# DAC5682.net
KiCad netlist of a schematic drawn in Altium Designer
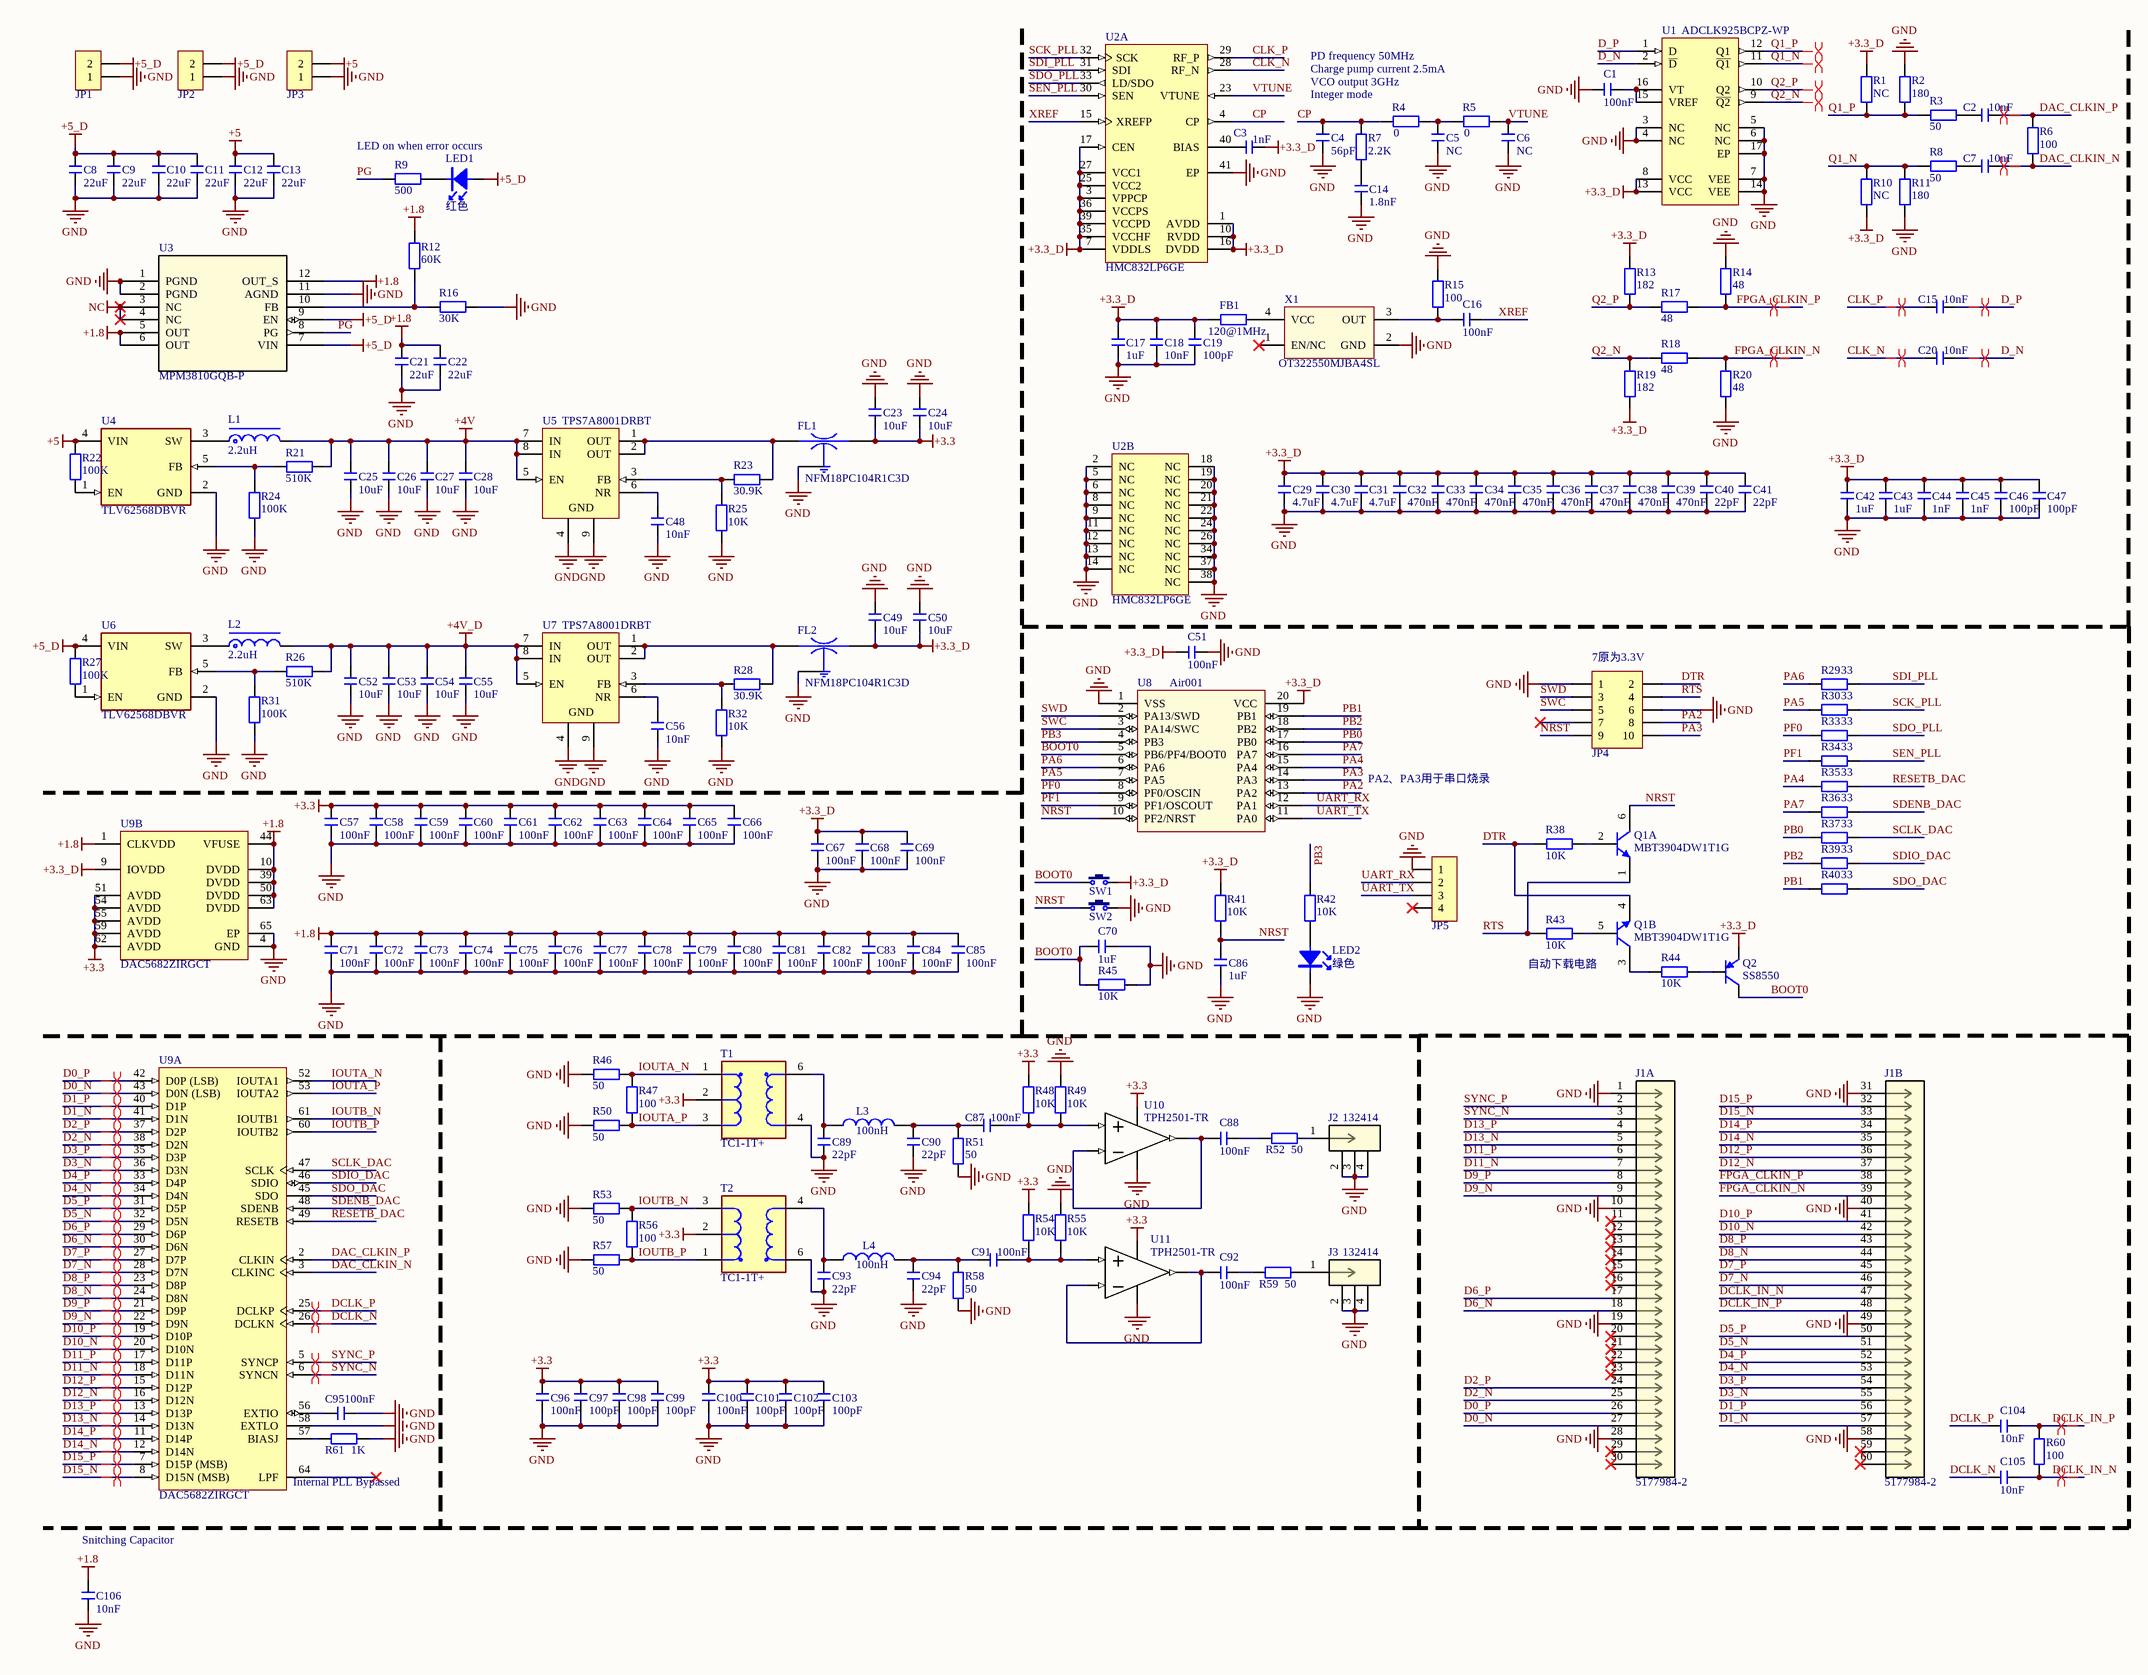
[diagram p0: DAC5682.SchDoc]

(export (version "E")
  (design (tool "Eeschema 10.0.6"))
  (components
    (comp (ref "C1")
      (value "100nF")
      (footprint "C 0402_L")
      (description "贴片电容")
      (libsource (lib "01 - 电容-电阻-电感") (part "C"))
    )
    (comp (ref "C2")
      (value "10nF")
      (footprint "C 0402_L")
      (description "贴片电容")
      (libsource (lib "01 - 电容-电阻-电感") (part "C"))
    )
    (comp (ref "C3")
      (value "1nF")
      (footprint "C 0402_L")
      (description "贴片电容")
      (libsource (lib "01 - 电容-电阻-电感") (part "C"))
    )
    (comp (ref "C4")
      (value "56pF")
      (footprint "C 0402_L")
      (description "贴片电容")
      (libsource (lib "01 - 电容-电阻-电感") (part "C"))
    )
    (comp (ref "C5")
      (value "NC")
      (footprint "C 0402_L")
      (description "贴片电容")
      (libsource (lib "01 - 电容-电阻-电感") (part "C"))
    )
    (comp (ref "C6")
      (value "NC")
      (footprint "C 0402_L")
      (description "贴片电容")
      (libsource (lib "01 - 电容-电阻-电感") (part "C"))
    )
    (comp (ref "C7")
      (value "10nF")
      (footprint "C 0402_L")
      (description "贴片电容")
      (libsource (lib "01 - 电容-电阻-电感") (part "C"))
    )
    (comp (ref "C8")
      (value "22uF")
      (footprint "C 1206_L")
      (description "贴片电容")
      (libsource (lib "01 - 电容-电阻-电感") (part "C"))
    )
    (comp (ref "C9")
      (value "22uF")
      (footprint "C 1206_L")
      (description "贴片电容")
      (libsource (lib "01 - 电容-电阻-电感") (part "C"))
    )
    (comp (ref "C10")
      (value "22uF")
      (footprint "C 1206_L")
      (description "贴片电容")
      (libsource (lib "01 - 电容-电阻-电感") (part "C"))
    )
    (comp (ref "C11")
      (value "22uF")
      (footprint "C 1206_L")
      (description "贴片电容")
      (libsource (lib "01 - 电容-电阻-电感") (part "C"))
    )
    (comp (ref "C12")
      (value "22uF")
      (footprint "C 1206_L")
      (description "贴片电容")
      (libsource (lib "01 - 电容-电阻-电感") (part "C"))
    )
    (comp (ref "C13")
      (value "22uF")
      (footprint "C 1206_L")
      (description "贴片电容")
      (libsource (lib "01 - 电容-电阻-电感") (part "C"))
    )
    (comp (ref "C14")
      (value "1.8nF")
      (footprint "C 0402_L")
      (description "贴片电容")
      (libsource (lib "01 - 电容-电阻-电感") (part "C"))
    )
    (comp (ref "C15")
      (value "10nF")
      (footprint "C 0402_L")
      (description "贴片电容")
      (libsource (lib "01 - 电容-电阻-电感") (part "C"))
    )
    (comp (ref "C16")
      (value "100nF")
      (footprint "C 0402_L")
      (description "贴片电容")
      (libsource (lib "01 - 电容-电阻-电感") (part "C"))
    )
    (comp (ref "C17")
      (value "1uF")
      (footprint "C 0402_L")
      (description "贴片电容")
      (libsource (lib "01 - 电容-电阻-电感") (part "C"))
    )
    (comp (ref "C18")
      (value "10nF")
      (footprint "C 0402_L")
      (description "贴片电容")
      (libsource (lib "01 - 电容-电阻-电感") (part "C"))
    )
    (comp (ref "C19")
      (value "100pF")
      (footprint "C 0402_L")
      (description "贴片电容")
      (libsource (lib "01 - 电容-电阻-电感") (part "C"))
    )
    (comp (ref "C20")
      (value "10nF")
      (footprint "C 0402_L")
      (description "贴片电容")
      (libsource (lib "01 - 电容-电阻-电感") (part "C"))
    )
    (comp (ref "C21")
      (value "22uF")
      (footprint "C 1206_L")
      (description "贴片电容")
      (libsource (lib "01 - 电容-电阻-电感") (part "C"))
    )
    (comp (ref "C22")
      (value "22uF")
      (footprint "C 1206_L")
      (description "贴片电容")
      (libsource (lib "01 - 电容-电阻-电感") (part "C"))
    )
    (comp (ref "C23")
      (value "10uF")
      (footprint "C 0805_L")
      (description "贴片电容")
      (libsource (lib "01 - 电容-电阻-电感") (part "C"))
    )
    (comp (ref "C24")
      (value "10uF")
      (footprint "C 0805_L")
      (description "贴片电容")
      (libsource (lib "01 - 电容-电阻-电感") (part "C"))
    )
    (comp (ref "C25")
      (value "10uF")
      (footprint "C 0805_L")
      (description "贴片电容")
      (libsource (lib "01 - 电容-电阻-电感") (part "C"))
    )
    (comp (ref "C26")
      (value "10uF")
      (footprint "C 0805_L")
      (description "贴片电容")
      (libsource (lib "01 - 电容-电阻-电感") (part "C"))
    )
    (comp (ref "C27")
      (value "10uF")
      (footprint "C 0805_L")
      (description "贴片电容")
      (libsource (lib "01 - 电容-电阻-电感") (part "C"))
    )
    (comp (ref "C28")
      (value "10uF")
      (footprint "C 0805_L")
      (description "贴片电容")
      (libsource (lib "01 - 电容-电阻-电感") (part "C"))
    )
    (comp (ref "C29")
      (value "4.7uF")
      (footprint "C 0603_L")
      (description "贴片电容")
      (libsource (lib "01 - 电容-电阻-电感") (part "C"))
    )
    (comp (ref "C30")
      (value "4.7uF")
      (footprint "C 0603_L")
      (description "贴片电容")
      (libsource (lib "01 - 电容-电阻-电感") (part "C"))
    )
    (comp (ref "C31")
      (value "4.7uF")
      (footprint "C 0603_L")
      (description "贴片电容")
      (libsource (lib "01 - 电容-电阻-电感") (part "C"))
    )
    (comp (ref "C32")
      (value "470nF")
      (footprint "C 0402_L")
      (description "贴片电容")
      (libsource (lib "01 - 电容-电阻-电感") (part "C"))
    )
    (comp (ref "C33")
      (value "470nF")
      (footprint "C 0402_L")
      (description "贴片电容")
      (libsource (lib "01 - 电容-电阻-电感") (part "C"))
    )
    (comp (ref "C34")
      (value "470nF")
      (footprint "C 0402_L")
      (description "贴片电容")
      (libsource (lib "01 - 电容-电阻-电感") (part "C"))
    )
    (comp (ref "C35")
      (value "470nF")
      (footprint "C 0402_L")
      (description "贴片电容")
      (libsource (lib "01 - 电容-电阻-电感") (part "C"))
    )
    (comp (ref "C36")
      (value "470nF")
      (footprint "C 0402_L")
      (description "贴片电容")
      (libsource (lib "01 - 电容-电阻-电感") (part "C"))
    )
    (comp (ref "C37")
      (value "470nF")
      (footprint "C 0402_L")
      (description "贴片电容")
      (libsource (lib "01 - 电容-电阻-电感") (part "C"))
    )
    (comp (ref "C38")
      (value "470nF")
      (footprint "C 0402_L")
      (description "贴片电容")
      (libsource (lib "01 - 电容-电阻-电感") (part "C"))
    )
    (comp (ref "C39")
      (value "470nF")
      (footprint "C 0402_L")
      (description "贴片电容")
      (libsource (lib "01 - 电容-电阻-电感") (part "C"))
    )
    (comp (ref "C40")
      (value "22pF")
      (footprint "C 0402_L")
      (description "贴片电容")
      (libsource (lib "01 - 电容-电阻-电感") (part "C"))
    )
    (comp (ref "C41")
      (value "22pF")
      (footprint "C 0402_L")
      (description "贴片电容")
      (libsource (lib "01 - 电容-电阻-电感") (part "C"))
    )
    (comp (ref "C42")
      (value "1uF")
      (footprint "C 0603_L")
      (description "贴片电容")
      (libsource (lib "01 - 电容-电阻-电感") (part "C"))
    )
    (comp (ref "C43")
      (value "1uF")
      (footprint "C 0603_L")
      (description "贴片电容")
      (libsource (lib "01 - 电容-电阻-电感") (part "C"))
    )
    (comp (ref "C44")
      (value "1nF")
      (footprint "C 0402_L")
      (description "贴片电容")
      (libsource (lib "01 - 电容-电阻-电感") (part "C"))
    )
    (comp (ref "C45")
      (value "1nF")
      (footprint "C 0402_L")
      (description "贴片电容")
      (libsource (lib "01 - 电容-电阻-电感") (part "C"))
    )
    (comp (ref "C46")
      (value "100pF")
      (footprint "C 0402_L")
      (description "贴片电容")
      (libsource (lib "01 - 电容-电阻-电感") (part "C"))
    )
    (comp (ref "C47")
      (value "100pF")
      (footprint "C 0402_L")
      (description "贴片电容")
      (libsource (lib "01 - 电容-电阻-电感") (part "C"))
    )
    (comp (ref "C48")
      (value "10nF")
      (footprint "C 0402_L")
      (description "贴片电容")
      (libsource (lib "01 - 电容-电阻-电感") (part "C"))
    )
    (comp (ref "C49")
      (value "10uF")
      (footprint "C 0805_L")
      (description "贴片电容")
      (libsource (lib "01 - 电容-电阻-电感") (part "C"))
    )
    (comp (ref "C50")
      (value "10uF")
      (footprint "C 0805_L")
      (description "贴片电容")
      (libsource (lib "01 - 电容-电阻-电感") (part "C"))
    )
    (comp (ref "C51")
      (value "100nF")
      (footprint "C 0402_L")
      (description "贴片电容")
      (libsource (lib "01 - 电容-电阻-电感") (part "C"))
    )
    (comp (ref "C52")
      (value "10uF")
      (footprint "C 0805_L")
      (description "贴片电容")
      (libsource (lib "01 - 电容-电阻-电感") (part "C"))
    )
    (comp (ref "C53")
      (value "10uF")
      (footprint "C 0805_L")
      (description "贴片电容")
      (libsource (lib "01 - 电容-电阻-电感") (part "C"))
    )
    (comp (ref "C54")
      (value "10uF")
      (footprint "C 0805_L")
      (description "贴片电容")
      (libsource (lib "01 - 电容-电阻-电感") (part "C"))
    )
    (comp (ref "C55")
      (value "10uF")
      (footprint "C 0805_L")
      (description "贴片电容")
      (libsource (lib "01 - 电容-电阻-电感") (part "C"))
    )
    (comp (ref "C56")
      (value "10nF")
      (footprint "C 0402_L")
      (description "贴片电容")
      (libsource (lib "01 - 电容-电阻-电感") (part "C"))
    )
    (comp (ref "C57")
      (value "100nF")
      (footprint "C 0402_L")
      (description "贴片电容")
      (libsource (lib "01 - 电容-电阻-电感") (part "C"))
    )
    (comp (ref "C58")
      (value "100nF")
      (footprint "C 0402_L")
      (description "贴片电容")
      (libsource (lib "01 - 电容-电阻-电感") (part "C"))
    )
    (comp (ref "C59")
      (value "100nF")
      (footprint "C 0402_L")
      (description "贴片电容")
      (libsource (lib "01 - 电容-电阻-电感") (part "C"))
    )
    (comp (ref "C60")
      (value "100nF")
      (footprint "C 0402_L")
      (description "贴片电容")
      (libsource (lib "01 - 电容-电阻-电感") (part "C"))
    )
    (comp (ref "C61")
      (value "100nF")
      (footprint "C 0402_L")
      (description "贴片电容")
      (libsource (lib "01 - 电容-电阻-电感") (part "C"))
    )
    (comp (ref "C62")
      (value "100nF")
      (footprint "C 0402_L")
      (description "贴片电容")
      (libsource (lib "01 - 电容-电阻-电感") (part "C"))
    )
    (comp (ref "C63")
      (value "100nF")
      (footprint "C 0402_L")
      (description "贴片电容")
      (libsource (lib "01 - 电容-电阻-电感") (part "C"))
    )
    (comp (ref "C64")
      (value "100nF")
      (footprint "C 0402_L")
      (description "贴片电容")
      (libsource (lib "01 - 电容-电阻-电感") (part "C"))
    )
    (comp (ref "C65")
      (value "100nF")
      (footprint "C 0402_L")
      (description "贴片电容")
      (libsource (lib "01 - 电容-电阻-电感") (part "C"))
    )
    (comp (ref "C66")
      (value "100nF")
      (footprint "C 0402_L")
      (description "贴片电容")
      (libsource (lib "01 - 电容-电阻-电感") (part "C"))
    )
    (comp (ref "C67")
      (value "100nF")
      (footprint "C 0402_L")
      (description "贴片电容")
      (libsource (lib "01 - 电容-电阻-电感") (part "C"))
    )
    (comp (ref "C68")
      (value "100nF")
      (footprint "C 0402_L")
      (description "贴片电容")
      (libsource (lib "01 - 电容-电阻-电感") (part "C"))
    )
    (comp (ref "C69")
      (value "100nF")
      (footprint "C 0402_L")
      (description "贴片电容")
      (libsource (lib "01 - 电容-电阻-电感") (part "C"))
    )
    (comp (ref "C70")
      (value "1uF")
      (footprint "C 0402_L")
      (description "贴片电容")
      (libsource (lib "01 - 电容-电阻-电感") (part "C"))
    )
    (comp (ref "C71")
      (value "100nF")
      (footprint "C 0402_L")
      (description "贴片电容")
      (libsource (lib "01 - 电容-电阻-电感") (part "C"))
    )
    (comp (ref "C72")
      (value "100nF")
      (footprint "C 0402_L")
      (description "贴片电容")
      (libsource (lib "01 - 电容-电阻-电感") (part "C"))
    )
    (comp (ref "C73")
      (value "100nF")
      (footprint "C 0402_L")
      (description "贴片电容")
      (libsource (lib "01 - 电容-电阻-电感") (part "C"))
    )
    (comp (ref "C74")
      (value "100nF")
      (footprint "C 0402_L")
      (description "贴片电容")
      (libsource (lib "01 - 电容-电阻-电感") (part "C"))
    )
    (comp (ref "C75")
      (value "100nF")
      (footprint "C 0402_L")
      (description "贴片电容")
      (libsource (lib "01 - 电容-电阻-电感") (part "C"))
    )
    (comp (ref "C76")
      (value "100nF")
      (footprint "C 0402_L")
      (description "贴片电容")
      (libsource (lib "01 - 电容-电阻-电感") (part "C"))
    )
    (comp (ref "C77")
      (value "100nF")
      (footprint "C 0402_L")
      (description "贴片电容")
      (libsource (lib "01 - 电容-电阻-电感") (part "C"))
    )
    (comp (ref "C78")
      (value "100nF")
      (footprint "C 0402_L")
      (description "贴片电容")
      (libsource (lib "01 - 电容-电阻-电感") (part "C"))
    )
    (comp (ref "C79")
      (value "100nF")
      (footprint "C 0402_L")
      (description "贴片电容")
      (libsource (lib "01 - 电容-电阻-电感") (part "C"))
    )
    (comp (ref "C80")
      (value "100nF")
      (footprint "C 0402_L")
      (description "贴片电容")
      (libsource (lib "01 - 电容-电阻-电感") (part "C"))
    )
    (comp (ref "C81")
      (value "100nF")
      (footprint "C 0402_L")
      (description "贴片电容")
      (libsource (lib "01 - 电容-电阻-电感") (part "C"))
    )
    (comp (ref "C82")
      (value "100nF")
      (footprint "C 0402_L")
      (description "贴片电容")
      (libsource (lib "01 - 电容-电阻-电感") (part "C"))
    )
    (comp (ref "C83")
      (value "100nF")
      (footprint "C 0402_L")
      (description "贴片电容")
      (libsource (lib "01 - 电容-电阻-电感") (part "C"))
    )
    (comp (ref "C84")
      (value "100nF")
      (footprint "C 0402_L")
      (description "贴片电容")
      (libsource (lib "01 - 电容-电阻-电感") (part "C"))
    )
    (comp (ref "C85")
      (value "100nF")
      (footprint "C 0402_L")
      (description "贴片电容")
      (libsource (lib "01 - 电容-电阻-电感") (part "C"))
    )
    (comp (ref "C86")
      (value "1uF")
      (footprint "C 0402_L")
      (description "贴片电容")
      (libsource (lib "01 - 电容-电阻-电感") (part "C"))
    )
    (comp (ref "C87")
      (value "100nF")
      (footprint "C 0402_L")
      (description "贴片电容")
      (libsource (lib "01 - 电容-电阻-电感") (part "C"))
    )
    (comp (ref "C88")
      (value "100nF")
      (footprint "C 0402_L")
      (description "贴片电容")
      (libsource (lib "01 - 电容-电阻-电感") (part "C"))
    )
    (comp (ref "C89")
      (value "22pF")
      (footprint "C 0402_L")
      (description "贴片电容")
      (libsource (lib "01 - 电容-电阻-电感") (part "C"))
    )
    (comp (ref "C90")
      (value "22pF")
      (footprint "C 0402_L")
      (description "贴片电容")
      (libsource (lib "01 - 电容-电阻-电感") (part "C"))
    )
    (comp (ref "C91")
      (value "100nF")
      (footprint "C 0402_L")
      (description "贴片电容")
      (libsource (lib "01 - 电容-电阻-电感") (part "C"))
    )
    (comp (ref "C92")
      (value "100nF")
      (footprint "C 0402_L")
      (description "贴片电容")
      (libsource (lib "01 - 电容-电阻-电感") (part "C"))
    )
    (comp (ref "C93")
      (value "22pF")
      (footprint "C 0402_L")
      (description "贴片电容")
      (libsource (lib "01 - 电容-电阻-电感") (part "C"))
    )
    (comp (ref "C94")
      (value "22pF")
      (footprint "C 0402_L")
      (description "贴片电容")
      (libsource (lib "01 - 电容-电阻-电感") (part "C"))
    )
    (comp (ref "C95")
      (value "100nF")
      (footprint "C 0402_L")
      (description "贴片电容")
      (libsource (lib "01 - 电容-电阻-电感") (part "C"))
    )
    (comp (ref "C96")
      (value "100nF")
      (footprint "C 0402_L")
      (description "贴片电容")
      (libsource (lib "01 - 电容-电阻-电感") (part "C"))
    )
    (comp (ref "C97")
      (value "100pF")
      (footprint "C 0402_L")
      (description "贴片电容")
      (libsource (lib "01 - 电容-电阻-电感") (part "C"))
    )
    (comp (ref "C98")
      (value "100pF")
      (footprint "C 0402_L")
      (description "贴片电容")
      (libsource (lib "01 - 电容-电阻-电感") (part "C"))
    )
    (comp (ref "C99")
      (value "100pF")
      (footprint "C 0402_L")
      (description "贴片电容")
      (libsource (lib "01 - 电容-电阻-电感") (part "C"))
    )
    (comp (ref "C100")
      (value "100nF")
      (footprint "C 0402_L")
      (description "贴片电容")
      (libsource (lib "01 - 电容-电阻-电感") (part "C"))
    )
    (comp (ref "C101")
      (value "100pF")
      (footprint "C 0402_L")
      (description "贴片电容")
      (libsource (lib "01 - 电容-电阻-电感") (part "C"))
    )
    (comp (ref "C102")
      (value "100pF")
      (footprint "C 0402_L")
      (description "贴片电容")
      (libsource (lib "01 - 电容-电阻-电感") (part "C"))
    )
    (comp (ref "C103")
      (value "100pF")
      (footprint "C 0402_L")
      (description "贴片电容")
      (libsource (lib "01 - 电容-电阻-电感") (part "C"))
    )
    (comp (ref "C104")
      (value "10nF")
      (footprint "C 0402_L")
      (description "贴片电容")
      (libsource (lib "01 - 电容-电阻-电感") (part "C"))
    )
    (comp (ref "C105")
      (value "10nF")
      (footprint "C 0402_L")
      (description "贴片电容")
      (libsource (lib "01 - 电容-电阻-电感") (part "C"))
    )
    (comp (ref "C106")
      (value "10nF")
      (footprint "C 0402_L")
      (description "贴片电容")
      (libsource (lib "01 - 电容-电阻-电感") (part "C"))
    )
    (comp (ref "FB1")
      (value "120@1MHz")
      (footprint "R 0603_L")
      (description "贴片电阻")
      (libsource (lib "01 - 电容-电阻-电感") (part "R"))
    )
    (comp (ref "FL1")
      (value "NFM18PC104R1C3D")
      (footprint "FIL_NFM18PC104R1C3D")
      (description "SMD Capacitor with Capacitance: 0.10uF Tol. 20%. Rated Voltage: 16Vdc")
      (fields (field (name "MF") "Murata") (field (name "DIGI-KEY_PART_NUMBER") "490-6969-1-ND"))
      (libsource (lib "NFM18PC104R1C3D") (part "NFM18PC104R1C3D"))
    )
    (comp (ref "FL2")
      (value "NFM18PC104R1C3D")
      (footprint "FIL_NFM18PC104R1C3D")
      (description "SMD Capacitor with Capacitance: 0.10uF Tol. 20%. Rated Voltage: 16Vdc")
      (fields (field (name "MF") "Murata") (field (name "DIGI-KEY_PART_NUMBER") "490-6969-1-ND"))
      (libsource (lib "NFM18PC104R1C3D") (part "NFM18PC104R1C3D"))
    )
    (comp (ref "J1")
      (value "5177984-2")
      (footprint "CONN_5177984-2_TYC")
      (description "No Description Available")
      (fields (field (name "COPYRIGHT") "Copyright (C) 2022 Ultra Librarian. All rights reserved."))
      (libsource (lib "5177984-2") (part "5177984-2"))
    )
    (comp (ref "J2")
      (value "132414")
      (footprint "CONN_132414_AMP")
      (description "No Description Available")
      (fields (field (name "COPYRIGHT") "Copyright (C) 2022 Ultra Librarian. All rights reserved."))
      (libsource (lib "细针大偏脚SMA(用这个)") (part "132414"))
    )
    (comp (ref "J3")
      (value "132414")
      (footprint "CONN_132414_AMP")
      (description "No Description Available")
      (fields (field (name "COPYRIGHT") "Copyright (C) 2022 Ultra Librarian. All rights reserved."))
      (libsource (lib "细针大偏脚SMA(用这个)") (part "132414"))
    )
    (comp (ref "JP1")
      (value "HDR-1X2")
      (footprint "KF2510-LI-2P")
      (description "2P接插件")
      (libsource (lib "18 - 接插件-脚距2.54mm (100mil) ") (part "Header 2"))
    )
    (comp (ref "JP2")
      (value "HDR-1X2")
      (footprint "KF2510-LI-2P")
      (description "2P接插件")
      (libsource (lib "18 - 接插件-脚距2.54mm (100mil) ") (part "Header 2"))
    )
    (comp (ref "JP3")
      (value "HDR-1X2")
      (footprint "KF2510-LI-2P")
      (description "2P接插件")
      (libsource (lib "18 - 接插件-脚距2.54mm (100mil) ") (part "Header 2"))
    )
    (comp (ref "JP4")
      (value "Header 5X2")
      (footprint "HDR2.54-M-LS-2x5P")
      (description "5*2P接插件")
      (libsource (lib "18 - 接插件-脚距2.54mm (100mil) ") (part "Header 5X2"))
    )
    (comp (ref "JP5")
      (value "HDR-1X4")
      (footprint "XH2.54-WS-4P")
      (description "4P接插件")
      (libsource (lib "18 - 接插件-脚距2.54mm (100mil) ") (part "Header 4"))
    )
    (comp (ref "L1")
      (value "2.2uH")
      (footprint "L-SMD-0630")
      (description "功率屏蔽电感")
      (libsource (lib "01 - 电容-电阻-电感") (part "L-CDRH"))
    )
    (comp (ref "L2")
      (value "2.2uH")
      (footprint "L-SMD-0630")
      (description "功率屏蔽电感")
      (libsource (lib "01 - 电容-电阻-电感") (part "L-CDRH"))
    )
    (comp (ref "L3")
      (value "100nH")
      (footprint "L 0603")
      (description "小功率贴片电感")
      (libsource (lib "01 - 电容-电阻-电感") (part "L"))
    )
    (comp (ref "L4")
      (value "100nH")
      (footprint "L 0603")
      (description "小功率贴片电感")
      (libsource (lib "01 - 电容-电阻-电感") (part "L"))
    )
    (comp (ref "LED1")
      (value "红色")
      (footprint "LED 0603R")
      (description "贴片LED")
      (libsource (lib "02 - 二极管(LED)-三极管-整流桥") (part "LED-SMD"))
    )
    (comp (ref "LED2")
      (value "绿色")
      (footprint "LED 0603G")
      (description "贴片LED")
      (libsource (lib "02 - 二极管(LED)-三极管-整流桥") (part "LED-SMD"))
    )
    (comp (ref "Q1")
      (value "MBT3904DW1T1G")
      (footprint "ONSC-SOT-363-6-419B-02_W_V")
      (description "Dual General Purpose Transistors, 6-Pin SOT-363, Pb-Free, Tape and Reel")
      (fields (field (name "MANUFACTURER") "On Semiconductor"))
      (libsource (lib "MBT3904DW1T1G") (part "CMP-1048-00877-1"))
    )
    (comp (ref "Q2")
      (value "SS8550")
      (footprint "SOT23-3L")
      (description "高频放大-PNP型")
      (libsource (lib "02 - 二极管(LED)-三极管-整流桥") (part "8550-SMD"))
    )
    (comp (ref "R1")
      (value "NC")
      (footprint "R 0402_L")
      (description "贴片电阻")
      (libsource (lib "01 - 电容-电阻-电感") (part "R"))
    )
    (comp (ref "R2")
      (value "180")
      (footprint "R 0402_L")
      (description "贴片电阻")
      (libsource (lib "01 - 电容-电阻-电感") (part "R"))
    )
    (comp (ref "R3")
      (value "50")
      (footprint "R 0402_L")
      (description "贴片电阻")
      (libsource (lib "01 - 电容-电阻-电感") (part "R"))
    )
    (comp (ref "R4")
      (value "0")
      (footprint "R 0402_L")
      (description "贴片电阻")
      (libsource (lib "01 - 电容-电阻-电感") (part "R"))
    )
    (comp (ref "R5")
      (value "0")
      (footprint "R 0402_L")
      (description "贴片电阻")
      (libsource (lib "01 - 电容-电阻-电感") (part "R"))
    )
    (comp (ref "R6")
      (value "100")
      (footprint "R 0402_L")
      (description "贴片电阻")
      (libsource (lib "01 - 电容-电阻-电感") (part "R"))
    )
    (comp (ref "R7")
      (value "2.2K")
      (footprint "R 0402_L")
      (description "贴片电阻")
      (libsource (lib "01 - 电容-电阻-电感") (part "R"))
    )
    (comp (ref "R8")
      (value "50")
      (footprint "R 0402_L")
      (description "贴片电阻")
      (libsource (lib "01 - 电容-电阻-电感") (part "R"))
    )
    (comp (ref "R9")
      (value "500")
      (footprint "R 0402_L")
      (description "贴片电阻")
      (libsource (lib "01 - 电容-电阻-电感") (part "R"))
    )
    (comp (ref "R10")
      (value "NC")
      (footprint "R 0402_L")
      (description "贴片电阻")
      (libsource (lib "01 - 电容-电阻-电感") (part "R"))
    )
    (comp (ref "R11")
      (value "180")
      (footprint "R 0402_L")
      (description "贴片电阻")
      (libsource (lib "01 - 电容-电阻-电感") (part "R"))
    )
    (comp (ref "R12")
      (value "60K")
      (footprint "R 0402_L")
      (description "贴片电阻")
      (libsource (lib "01 - 电容-电阻-电感") (part "R"))
    )
    (comp (ref "R13")
      (value "182")
      (footprint "R 0402_L")
      (description "贴片电阻")
      (libsource (lib "01 - 电容-电阻-电感") (part "R"))
    )
    (comp (ref "R14")
      (value "48")
      (footprint "R 0402_L")
      (description "贴片电阻")
      (libsource (lib "01 - 电容-电阻-电感") (part "R"))
    )
    (comp (ref "R15")
      (value "100")
      (footprint "R 0402_L")
      (description "贴片电阻")
      (libsource (lib "01 - 电容-电阻-电感") (part "R"))
    )
    (comp (ref "R16")
      (value "30K")
      (footprint "R 0402_L")
      (description "贴片电阻")
      (libsource (lib "01 - 电容-电阻-电感") (part "R"))
    )
    (comp (ref "R17")
      (value "48")
      (footprint "R 0402_L")
      (description "贴片电阻")
      (libsource (lib "01 - 电容-电阻-电感") (part "R"))
    )
    (comp (ref "R18")
      (value "48")
      (footprint "R 0402_L")
      (description "贴片电阻")
      (libsource (lib "01 - 电容-电阻-电感") (part "R"))
    )
    (comp (ref "R19")
      (value "182")
      (footprint "R 0402_L")
      (description "贴片电阻")
      (libsource (lib "01 - 电容-电阻-电感") (part "R"))
    )
    (comp (ref "R20")
      (value "48")
      (footprint "R 0402_L")
      (description "贴片电阻")
      (libsource (lib "01 - 电容-电阻-电感") (part "R"))
    )
    (comp (ref "R21")
      (value "510K")
      (footprint "R 0402_L")
      (description "贴片电阻")
      (libsource (lib "01 - 电容-电阻-电感") (part "R"))
    )
    (comp (ref "R22")
      (value "100K")
      (footprint "R 0402_L")
      (description "贴片电阻")
      (libsource (lib "01 - 电容-电阻-电感") (part "R"))
    )
    (comp (ref "R23")
      (value "30.9K")
      (footprint "R 0402_L")
      (description "贴片电阻")
      (libsource (lib "01 - 电容-电阻-电感") (part "R"))
    )
    (comp (ref "R24")
      (value "100K")
      (footprint "R 0402_L")
      (description "贴片电阻")
      (libsource (lib "01 - 电容-电阻-电感") (part "R"))
    )
    (comp (ref "R25")
      (value "10K")
      (footprint "R 0402_L")
      (description "贴片电阻")
      (libsource (lib "01 - 电容-电阻-电感") (part "R"))
    )
    (comp (ref "R26")
      (value "510K")
      (footprint "R 0402_L")
      (description "贴片电阻")
      (libsource (lib "01 - 电容-电阻-电感") (part "R"))
    )
    (comp (ref "R27")
      (value "100K")
      (footprint "R 0402_L")
      (description "贴片电阻")
      (libsource (lib "01 - 电容-电阻-电感") (part "R"))
    )
    (comp (ref "R28")
      (value "30.9K")
      (footprint "R 0402_L")
      (description "贴片电阻")
      (libsource (lib "01 - 电容-电阻-电感") (part "R"))
    )
    (comp (ref "R29")
      (value "33")
      (footprint "R 0402_L")
      (description "贴片电阻")
      (libsource (lib "01 - 电容-电阻-电感") (part "R"))
    )
    (comp (ref "R30")
      (value "33")
      (footprint "R 0402_L")
      (description "贴片电阻")
      (libsource (lib "01 - 电容-电阻-电感") (part "R"))
    )
    (comp (ref "R31")
      (value "100K")
      (footprint "R 0402_L")
      (description "贴片电阻")
      (libsource (lib "01 - 电容-电阻-电感") (part "R"))
    )
    (comp (ref "R32")
      (value "10K")
      (footprint "R 0402_L")
      (description "贴片电阻")
      (libsource (lib "01 - 电容-电阻-电感") (part "R"))
    )
    (comp (ref "R33")
      (value "33")
      (footprint "R 0402_L")
      (description "贴片电阻")
      (libsource (lib "01 - 电容-电阻-电感") (part "R"))
    )
    (comp (ref "R34")
      (value "33")
      (footprint "R 0402_L")
      (description "贴片电阻")
      (libsource (lib "01 - 电容-电阻-电感") (part "R"))
    )
    (comp (ref "R35")
      (value "33")
      (footprint "R 0402_L")
      (description "贴片电阻")
      (libsource (lib "01 - 电容-电阻-电感") (part "R"))
    )
    (comp (ref "R36")
      (value "33")
      (footprint "R 0402_L")
      (description "贴片电阻")
      (libsource (lib "01 - 电容-电阻-电感") (part "R"))
    )
    (comp (ref "R37")
      (value "33")
      (footprint "R 0402_L")
      (description "贴片电阻")
      (libsource (lib "01 - 电容-电阻-电感") (part "R"))
    )
    (comp (ref "R38")
      (value "10K")
      (footprint "R 0402_L")
      (description "贴片电阻")
      (libsource (lib "01 - 电容-电阻-电感") (part "R"))
    )
    (comp (ref "R39")
      (value "33")
      (footprint "R 0402_L")
      (description "贴片电阻")
      (libsource (lib "01 - 电容-电阻-电感") (part "R"))
    )
    (comp (ref "R40")
      (value "33")
      (footprint "R 0402_L")
      (description "贴片电阻")
      (libsource (lib "01 - 电容-电阻-电感") (part "R"))
    )
    (comp (ref "R41")
      (value "10K")
      (footprint "R 0402_L")
      (description "贴片电阻")
      (libsource (lib "01 - 电容-电阻-电感") (part "R"))
    )
    (comp (ref "R42")
      (value "10K")
      (footprint "R 0402_L")
      (description "贴片电阻")
      (libsource (lib "01 - 电容-电阻-电感") (part "R"))
    )
    (comp (ref "R43")
      (value "10K")
      (footprint "R 0402_L")
      (description "贴片电阻")
      (libsource (lib "01 - 电容-电阻-电感") (part "R"))
    )
    (comp (ref "R44")
      (value "10K")
      (footprint "R 0402_L")
      (description "贴片电阻")
      (libsource (lib "01 - 电容-电阻-电感") (part "R"))
    )
    (comp (ref "R45")
      (value "10K")
      (footprint "R 0402_L")
      (description "贴片电阻")
      (libsource (lib "01 - 电容-电阻-电感") (part "R"))
    )
    (comp (ref "R46")
      (value "50")
      (footprint "R 0402_L")
      (description "贴片电阻")
      (libsource (lib "01 - 电容-电阻-电感") (part "R"))
    )
    (comp (ref "R47")
      (value "100")
      (footprint "R 0402_L")
      (description "贴片电阻")
      (libsource (lib "01 - 电容-电阻-电感") (part "R"))
    )
    (comp (ref "R48")
      (value "10K")
      (footprint "R 0402_L")
      (description "贴片电阻")
      (libsource (lib "01 - 电容-电阻-电感") (part "R"))
    )
    (comp (ref "R49")
      (value "10K")
      (footprint "R 0402_L")
      (description "贴片电阻")
      (libsource (lib "01 - 电容-电阻-电感") (part "R"))
    )
    (comp (ref "R50")
      (value "50")
      (footprint "R 0402_L")
      (description "贴片电阻")
      (libsource (lib "01 - 电容-电阻-电感") (part "R"))
    )
    (comp (ref "R51")
      (value "50")
      (footprint "R 0402_L")
      (description "贴片电阻")
      (libsource (lib "01 - 电容-电阻-电感") (part "R"))
    )
    (comp (ref "R52")
      (value "50")
      (footprint "R 0402_L")
      (description "贴片电阻")
      (libsource (lib "01 - 电容-电阻-电感") (part "R"))
    )
    (comp (ref "R53")
      (value "50")
      (footprint "R 0402_L")
      (description "贴片电阻")
      (libsource (lib "01 - 电容-电阻-电感") (part "R"))
    )
    (comp (ref "R54")
      (value "10K")
      (footprint "R 0402_L")
      (description "贴片电阻")
      (libsource (lib "01 - 电容-电阻-电感") (part "R"))
    )
    (comp (ref "R55")
      (value "10K")
      (footprint "R 0402_L")
      (description "贴片电阻")
      (libsource (lib "01 - 电容-电阻-电感") (part "R"))
    )
    (comp (ref "R56")
      (value "100")
      (footprint "R 0402_L")
      (description "贴片电阻")
      (libsource (lib "01 - 电容-电阻-电感") (part "R"))
    )
    (comp (ref "R57")
      (value "50")
      (footprint "R 0402_L")
      (description "贴片电阻")
      (libsource (lib "01 - 电容-电阻-电感") (part "R"))
    )
    (comp (ref "R58")
      (value "50")
      (footprint "R 0402_L")
      (description "贴片电阻")
      (libsource (lib "01 - 电容-电阻-电感") (part "R"))
    )
    (comp (ref "R59")
      (value "50")
      (footprint "R 0402_L")
      (description "贴片电阻")
      (libsource (lib "01 - 电容-电阻-电感") (part "R"))
    )
    (comp (ref "R60")
      (value "100")
      (footprint "R 0402_L")
      (description "贴片电阻")
      (libsource (lib "01 - 电容-电阻-电感") (part "R"))
    )
    (comp (ref "R61")
      (value "1K")
      (footprint "R 0402_L")
      (description "贴片电阻")
      (libsource (lib "01 - 电容-电阻-电感") (part "R"))
    )
    (comp (ref "SW1")
      (value "3x6x5")
      (footprint "TSW SMD-3*6*2.5")
      (description "3x6轻触开关")
      (libsource (lib "03 - 按键-开关-晶振-蜂鸣器") (part "TSW 3x6"))
    )
    (comp (ref "SW2")
      (value "3x6x5")
      (footprint "TSW SMD-3*6*2.5")
      (description "3x6轻触开关")
      (libsource (lib "03 - 按键-开关-晶振-蜂鸣器") (part "TSW 3x6"))
    )
    (comp (ref "T1")
      (value "TC1-1T+")
      (footprint "FP-TC1-1-13M+-MFG")
      (description "RF Transformer 1: 1 5 Terminal SMD")
      (libsource (lib "") (part "CMP-00025-00004-7_1"))
    )
    (comp (ref "T2")
      (value "TC1-1T+")
      (footprint "FP-TC1-1-13M+-MFG")
      (description "RF Transformer 1: 1 5 Terminal SMD")
      (libsource (lib "TC1-1T+") (part "CMP-00025-00004-7"))
    )
    (comp (ref "U1")
      (value "ADCLK925BCPZ-WP")
      (footprint "ADI-CP-16-3_L")
      (description "Ultrafast SiGe ECL Clock/Data Buffers, CP-16-3, Pb-Free, 50 Tray")
      (libsource (lib "ADCLK925BCPZ") (part "CMP-0288-00091-1"))
    )
    (comp (ref "U2")
      (value "HMC832LP6GE")
      (footprint "ADI-LP6G-40_L")
      (libsource (lib "HMC832ALP6GE") (part "CMP-0287-00184-1"))
    )
    (comp (ref "U3")
      (value "MPM3810GQB-P")
      (footprint "QFN2p5x3p0x0p9_MNP")
      (description "6V Input, 1.2A Module,Synchronous Step-Down Converter,with Integrated Inductor")
      (libsource (lib "MPM3810GQB") (part "MPM3810GQB-P"))
    )
    (comp (ref "U4")
      (value "TLV62568DBVR")
      (footprint "FP-DBV0005A-MFG")
      (description "IC REG BUCK ADJ 1A SOT23-5")
      (fields
        (field (name "MANUFACTURER") "Texas Instruments")
        (field (name "OCTOPART") "https://octopart.com/tlv62568dbvr-texas+instruments-76926199")
      )
      (libsource (lib "TLV62568DBVR") (part "CMP-04918-000009-1"))
    )
    (comp (ref "U5")
      (value "TPS7A8001DRBT")
      (footprint "DRB0008A_V")
      (fields (field (name "MANUFACTURER") "Texas Instruments"))
      (libsource (lib "TPS7A8001DRBT") (part "CMP-0395-00597-2"))
    )
    (comp (ref "U6")
      (value "TLV62568DBVR")
      (footprint "FP-DBV0005A-MFG")
      (description "IC REG BUCK ADJ 1A SOT23-5")
      (fields
        (field (name "MANUFACTURER") "Texas Instruments")
        (field (name "OCTOPART") "https://octopart.com/tlv62568dbvr-texas+instruments-76926199")
      )
      (libsource (lib "TLV62568DBVR") (part "CMP-04918-000009-1"))
    )
    (comp (ref "U7")
      (value "TPS7A8001DRBT")
      (footprint "DRB0008A_V")
      (fields (field (name "MANUFACTURER") "Texas Instruments"))
      (libsource (lib "TPS7A8001DRBT") (part "CMP-0395-00597-2"))
    )
    (comp (ref "U8") (value "Air001") (footprint "TSSOP20_L") (libsource (lib "Air001") (part "Air001")))
    (comp (ref "U9")
      (value "DAC5682ZIRGCT")
      (footprint "TI-RGC64-7400X7400TP_V")
      (fields (field (name "MANUFACTURER") "Texas Instruments"))
      (libsource (lib "DAC5682ZIRGCT") (part "CMP-0004-01427-1"))
    )
    (comp (ref "U10")
      (value "TPH2501-TR")
      (footprint "SOT23-5")
      (libsource (lib "TPH2501-TR") (part "TPH2501-TR"))
    )
    (comp (ref "U11")
      (value "TPH2501-TR")
      (footprint "SOT23-5")
      (libsource (lib "TPH2501-TR") (part "TPH2501-TR"))
    )
    (comp (ref "X1")
      (value "OT322550MJBA4SL")
      (footprint "OSC 3225-4P")
      (description "4脚有源晶振")
      (libsource (lib "03 - 按键-开关-晶振-蜂鸣器") (part "XTAL-ACT-4P"))
    )
  )
  (nets
    (net (code "1") (name "+1.8") (class "Default")
      (node (ref "C106") (pin "2") (pinfunction "2_2") (pintype "passive"))
      (node (ref "C21") (pin "2") (pinfunction "2_2") (pintype "passive"))
      (node (ref "C22") (pin "2") (pinfunction "2_2") (pintype "passive"))
      (node (ref "C71") (pin "2") (pinfunction "2_2") (pintype "passive"))
      (node (ref "C72") (pin "2") (pinfunction "2_2") (pintype "passive"))
      (node (ref "C73") (pin "2") (pinfunction "2_2") (pintype "passive"))
      (node (ref "C74") (pin "2") (pinfunction "2_2") (pintype "passive"))
      (node (ref "C75") (pin "2") (pinfunction "2_2") (pintype "passive"))
      (node (ref "C76") (pin "2") (pinfunction "2_2") (pintype "passive"))
      (node (ref "C77") (pin "2") (pinfunction "2_2") (pintype "passive"))
      (node (ref "C78") (pin "2") (pinfunction "2_2") (pintype "passive"))
      (node (ref "C79") (pin "2") (pinfunction "2_2") (pintype "passive"))
      (node (ref "C80") (pin "2") (pinfunction "2_2") (pintype "passive"))
      (node (ref "C81") (pin "2") (pinfunction "2_2") (pintype "passive"))
      (node (ref "C82") (pin "2") (pinfunction "2_2") (pintype "passive"))
      (node (ref "C83") (pin "2") (pinfunction "2_2") (pintype "passive"))
      (node (ref "C84") (pin "2") (pinfunction "2_2") (pintype "passive"))
      (node (ref "C85") (pin "2") (pinfunction "2_2") (pintype "passive"))
      (node (ref "R12") (pin "2") (pinfunction "2_2") (pintype "passive"))
      (node (ref "U3") (pin "12") (pinfunction "OUT_S_12") (pintype "passive"))
      (node (ref "U3") (pin "5") (pinfunction "OUT_5") (pintype "power_in"))
      (node (ref "U3") (pin "6") (pinfunction "OUT_6") (pintype "power_in"))
      (node (ref "U9") (pin "1") (pinfunction "CLKVDD_1") (pintype "power_in"))
      (node (ref "U9") (pin "10") (pinfunction "DVDD_10") (pintype "power_in"))
      (node (ref "U9") (pin "39") (pinfunction "DVDD_39") (pintype "power_in"))
      (node (ref "U9") (pin "44") (pinfunction "VFUSE_44") (pintype "power_in"))
      (node (ref "U9") (pin "50") (pinfunction "DVDD_50") (pintype "power_in"))
      (node (ref "U9") (pin "63") (pinfunction "DVDD_63") (pintype "power_in"))
    )
    (net (code "2") (name "+3.3") (class "Default")
      (node (ref "C100") (pin "2") (pinfunction "2_2") (pintype "passive"))
      (node (ref "C101") (pin "2") (pinfunction "2_2") (pintype "passive"))
      (node (ref "C102") (pin "2") (pinfunction "2_2") (pintype "passive"))
      (node (ref "C103") (pin "2") (pinfunction "2_2") (pintype "passive"))
      (node (ref "C23") (pin "1") (pinfunction "1_1") (pintype "passive"))
      (node (ref "C24") (pin "1") (pinfunction "1_1") (pintype "passive"))
      (node (ref "C57") (pin "2") (pinfunction "2_2") (pintype "passive"))
      (node (ref "C58") (pin "2") (pinfunction "2_2") (pintype "passive"))
      (node (ref "C59") (pin "2") (pinfunction "2_2") (pintype "passive"))
      (node (ref "C60") (pin "2") (pinfunction "2_2") (pintype "passive"))
      (node (ref "C61") (pin "2") (pinfunction "2_2") (pintype "passive"))
      (node (ref "C62") (pin "2") (pinfunction "2_2") (pintype "passive"))
      (node (ref "C63") (pin "2") (pinfunction "2_2") (pintype "passive"))
      (node (ref "C64") (pin "2") (pinfunction "2_2") (pintype "passive"))
      (node (ref "C65") (pin "2") (pinfunction "2_2") (pintype "passive"))
      (node (ref "C66") (pin "2") (pinfunction "2_2") (pintype "passive"))
      (node (ref "C96") (pin "2") (pinfunction "2_2") (pintype "passive"))
      (node (ref "C97") (pin "2") (pinfunction "2_2") (pintype "passive"))
      (node (ref "C98") (pin "2") (pinfunction "2_2") (pintype "passive"))
      (node (ref "C99") (pin "2") (pinfunction "2_2") (pintype "passive"))
      (node (ref "FL1") (pin "3") (pinfunction "OUT_3") (pintype "passive"))
      (node (ref "R48") (pin "2") (pinfunction "2_2") (pintype "passive"))
      (node (ref "R54") (pin "2") (pinfunction "2_2") (pintype "passive"))
      (node (ref "T1") (pin "2") (pinfunction "SECONDARY_2") (pintype "passive"))
      (node (ref "T2") (pin "2") (pinfunction "SECONDARY_2") (pintype "passive"))
      (node (ref "U10") (pin "5") (pinfunction "+Vs_5") (pintype "power_in"))
      (node (ref "U11") (pin "5") (pinfunction "+Vs_5") (pintype "power_in"))
      (node (ref "U9") (pin "51") (pinfunction "AVDD_51") (pintype "power_in"))
      (node (ref "U9") (pin "54") (pinfunction "AVDD_54") (pintype "power_in"))
      (node (ref "U9") (pin "55") (pinfunction "AVDD_55") (pintype "power_in"))
      (node (ref "U9") (pin "59") (pinfunction "AVDD_59") (pintype "power_in"))
      (node (ref "U9") (pin "62") (pinfunction "AVDD_62") (pintype "power_in"))
    )
    (net (code "3") (name "+3.3_D") (class "Default")
      (node (ref "C17") (pin "2") (pinfunction "2_2") (pintype "passive"))
      (node (ref "C18") (pin "2") (pinfunction "2_2") (pintype "passive"))
      (node (ref "C19") (pin "2") (pinfunction "2_2") (pintype "passive"))
      (node (ref "C29") (pin "2") (pinfunction "2_2") (pintype "passive"))
      (node (ref "C3") (pin "1") (pinfunction "1_1") (pintype "passive"))
      (node (ref "C30") (pin "2") (pinfunction "2_2") (pintype "passive"))
      (node (ref "C31") (pin "2") (pinfunction "2_2") (pintype "passive"))
      (node (ref "C32") (pin "2") (pinfunction "2_2") (pintype "passive"))
      (node (ref "C33") (pin "2") (pinfunction "2_2") (pintype "passive"))
      (node (ref "C34") (pin "2") (pinfunction "2_2") (pintype "passive"))
      (node (ref "C35") (pin "2") (pinfunction "2_2") (pintype "passive"))
      (node (ref "C36") (pin "2") (pinfunction "2_2") (pintype "passive"))
      (node (ref "C37") (pin "2") (pinfunction "2_2") (pintype "passive"))
      (node (ref "C38") (pin "2") (pinfunction "2_2") (pintype "passive"))
      (node (ref "C39") (pin "2") (pinfunction "2_2") (pintype "passive"))
      (node (ref "C40") (pin "2") (pinfunction "2_2") (pintype "passive"))
      (node (ref "C41") (pin "2") (pinfunction "2_2") (pintype "passive"))
      (node (ref "C42") (pin "2") (pinfunction "2_2") (pintype "passive"))
      (node (ref "C43") (pin "2") (pinfunction "2_2") (pintype "passive"))
      (node (ref "C44") (pin "2") (pinfunction "2_2") (pintype "passive"))
      (node (ref "C45") (pin "2") (pinfunction "2_2") (pintype "passive"))
      (node (ref "C46") (pin "2") (pinfunction "2_2") (pintype "passive"))
      (node (ref "C47") (pin "2") (pinfunction "2_2") (pintype "passive"))
      (node (ref "C49") (pin "1") (pinfunction "1_1") (pintype "passive"))
      (node (ref "C50") (pin "1") (pinfunction "1_1") (pintype "passive"))
      (node (ref "C51") (pin "1") (pinfunction "1_1") (pintype "passive"))
      (node (ref "C67") (pin "2") (pinfunction "2_2") (pintype "passive"))
      (node (ref "C68") (pin "2") (pinfunction "2_2") (pintype "passive"))
      (node (ref "C69") (pin "2") (pinfunction "2_2") (pintype "passive"))
      (node (ref "FB1") (pin "1") (pinfunction "1_1") (pintype "passive"))
      (node (ref "FL2") (pin "3") (pinfunction "OUT_3") (pintype "passive"))
      (node (ref "Q2") (pin "2") (pinfunction "E_2") (pintype "passive"))
      (node (ref "R1") (pin "2") (pinfunction "2_2") (pintype "passive"))
      (node (ref "R10") (pin "1") (pinfunction "1_1") (pintype "passive"))
      (node (ref "R13") (pin "2") (pinfunction "2_2") (pintype "passive"))
      (node (ref "R19") (pin "1") (pinfunction "1_1") (pintype "passive"))
      (node (ref "R41") (pin "1") (pinfunction "1_1") (pintype "passive"))
      (node (ref "SW1") (pin "2") (pinfunction "2_2") (pintype "passive"))
      (node (ref "U1") (pin "13") (pinfunction "VCC_13") (pintype "power_in"))
      (node (ref "U1") (pin "8") (pinfunction "VCC_8") (pintype "power_in"))
      (node (ref "U2") (pin "1") (pinfunction "AVDD_1") (pintype "power_in"))
      (node (ref "U2") (pin "10") (pinfunction "RVDD_10") (pintype "power_in"))
      (node (ref "U2") (pin "16") (pinfunction "DVDD_16") (pintype "power_in"))
      (node (ref "U2") (pin "17") (pinfunction "CEN_17") (pintype "input"))
      (node (ref "U2") (pin "25") (pinfunction "VCC2_25") (pintype "power_in"))
      (node (ref "U2") (pin "27") (pinfunction "VCC1_27") (pintype "power_in"))
      (node (ref "U2") (pin "3") (pinfunction "VPPCP_3") (pintype "power_in"))
      (node (ref "U2") (pin "35") (pinfunction "VCCHF_35") (pintype "power_in"))
      (node (ref "U2") (pin "36") (pinfunction "VCCPS_36") (pintype "power_in"))
      (node (ref "U2") (pin "39") (pinfunction "VCCPD_39") (pintype "power_in"))
      (node (ref "U2") (pin "7") (pinfunction "VDDLS_7") (pintype "power_in"))
      (node (ref "U8") (pin "20") (pinfunction "VCC_20") (pintype "power_in"))
      (node (ref "U9") (pin "9") (pinfunction "IOVDD_9") (pintype "power_in"))
    )
    (net (code "4") (name "+4V") (class "Default")
      (node (ref "C25") (pin "2") (pinfunction "2_2") (pintype "passive"))
      (node (ref "C26") (pin "2") (pinfunction "2_2") (pintype "passive"))
      (node (ref "C27") (pin "2") (pinfunction "2_2") (pintype "passive"))
      (node (ref "C28") (pin "2") (pinfunction "2_2") (pintype "passive"))
      (node (ref "L1") (pin "2") (pinfunction "2_2") (pintype "passive"))
      (node (ref "R21") (pin "1") (pinfunction "1_1") (pintype "passive"))
      (node (ref "U5") (pin "5") (pinfunction "EN_5") (pintype "input"))
      (node (ref "U5") (pin "7") (pinfunction "IN_7") (pintype "power_in"))
      (node (ref "U5") (pin "8") (pinfunction "IN_8") (pintype "power_in"))
    )
    (net (code "5") (name "+4V_D") (class "Default")
      (node (ref "C52") (pin "2") (pinfunction "2_2") (pintype "passive"))
      (node (ref "C53") (pin "2") (pinfunction "2_2") (pintype "passive"))
      (node (ref "C54") (pin "2") (pinfunction "2_2") (pintype "passive"))
      (node (ref "C55") (pin "2") (pinfunction "2_2") (pintype "passive"))
      (node (ref "L2") (pin "2") (pinfunction "2_2") (pintype "passive"))
      (node (ref "R26") (pin "1") (pinfunction "1_1") (pintype "passive"))
      (node (ref "U7") (pin "5") (pinfunction "EN_5") (pintype "input"))
      (node (ref "U7") (pin "7") (pinfunction "IN_7") (pintype "power_in"))
      (node (ref "U7") (pin "8") (pinfunction "IN_8") (pintype "power_in"))
    )
    (net (code "6") (name "+5") (class "Default")
      (node (ref "C12") (pin "2") (pinfunction "2_2") (pintype "passive"))
      (node (ref "C13") (pin "2") (pinfunction "2_2") (pintype "passive"))
      (node (ref "JP3") (pin "2") (pinfunction "2_2") (pintype "passive"))
      (node (ref "R22") (pin "1") (pinfunction "1_1") (pintype "passive"))
      (node (ref "U4") (pin "4") (pinfunction "VIN_4") (pintype "power_in"))
    )
    (net (code "7") (name "+5_D") (class "Default")
      (node (ref "C10") (pin "2") (pinfunction "2_2") (pintype "passive"))
      (node (ref "C11") (pin "2") (pinfunction "2_2") (pintype "passive"))
      (node (ref "C8") (pin "2") (pinfunction "2_2") (pintype "passive"))
      (node (ref "C9") (pin "2") (pinfunction "2_2") (pintype "passive"))
      (node (ref "JP1") (pin "2") (pinfunction "2_2") (pintype "passive"))
      (node (ref "JP2") (pin "2") (pinfunction "2_2") (pintype "passive"))
      (node (ref "LED1") (pin "1") (pinfunction "A_1") (pintype "passive"))
      (node (ref "R27") (pin "1") (pinfunction "1_1") (pintype "passive"))
      (node (ref "U3") (pin "7") (pinfunction "VIN_7") (pintype "power_in"))
      (node (ref "U3") (pin "9") (pinfunction "EN_9") (pintype "bidirectional"))
      (node (ref "U6") (pin "4") (pinfunction "VIN_4") (pintype "power_in"))
    )
    (net (code "8") (name "/BOOT0") (class "Default")
      (node (ref "C70") (pin "2") (pinfunction "2_2") (pintype "passive"))
      (node (ref "Q2") (pin "3") (pinfunction "C_3") (pintype "passive"))
      (node (ref "R45") (pin "2") (pinfunction "2_2") (pintype "passive"))
      (node (ref "SW1") (pin "1") (pinfunction "1_1") (pintype "passive"))
      (node (ref "U8") (pin "5") (pinfunction "PB6/PF4/BOOT0_5") (pintype "bidirectional"))
    )
    (net (code "9") (name "/CLK_N") (class "Default")
      (node (ref "C20") (pin "1") (pinfunction "1_1") (pintype "passive"))
      (node (ref "U2") (pin "28") (pinfunction "RF_N_28") (pintype "output"))
    )
    (net (code "10") (name "/CLK_P") (class "Default")
      (node (ref "C15") (pin "1") (pinfunction "1_1") (pintype "passive"))
      (node (ref "U2") (pin "29") (pinfunction "RF_P_29") (pintype "output"))
    )
    (net (code "11") (name "/CP") (class "Default")
      (node (ref "C4") (pin "2") (pinfunction "2_2") (pintype "passive"))
      (node (ref "R4") (pin "2") (pinfunction "2_2") (pintype "passive"))
      (node (ref "R7") (pin "2") (pinfunction "2_2") (pintype "passive"))
      (node (ref "U2") (pin "4") (pinfunction "CP_4") (pintype "output"))
    )
    (net (code "12") (name "/D0_N") (class "Default")
      (node (ref "J1") (pin "27") (pinfunction "27_27") (pintype "passive"))
      (node (ref "U9") (pin "43") (pinfunction "D0N_(LSB)_43") (pintype "input"))
    )
    (net (code "13") (name "/D0_P") (class "Default")
      (node (ref "J1") (pin "26") (pinfunction "26_26") (pintype "passive"))
      (node (ref "U9") (pin "42") (pinfunction "D0P_(LSB)_42") (pintype "input"))
    )
    (net (code "14") (name "/D1_N") (class "Default")
      (node (ref "J1") (pin "57") (pinfunction "57_57") (pintype "passive"))
      (node (ref "U9") (pin "41") (pinfunction "D1N_41") (pintype "input"))
    )
    (net (code "15") (name "/D1_P") (class "Default")
      (node (ref "J1") (pin "56") (pinfunction "56_56") (pintype "passive"))
      (node (ref "U9") (pin "40") (pinfunction "D1P_40") (pintype "input"))
    )
    (net (code "16") (name "/D2_N") (class "Default")
      (node (ref "J1") (pin "25") (pinfunction "25_25") (pintype "passive"))
      (node (ref "U9") (pin "38") (pinfunction "D2N_38") (pintype "input"))
    )
    (net (code "17") (name "/D2_P") (class "Default")
      (node (ref "J1") (pin "24") (pinfunction "24_24") (pintype "passive"))
      (node (ref "U9") (pin "37") (pinfunction "D2P_37") (pintype "input"))
    )
    (net (code "18") (name "/D3_N") (class "Default")
      (node (ref "J1") (pin "55") (pinfunction "55_55") (pintype "passive"))
      (node (ref "U9") (pin "36") (pinfunction "D3N_36") (pintype "input"))
    )
    (net (code "19") (name "/D3_P") (class "Default")
      (node (ref "J1") (pin "54") (pinfunction "54_54") (pintype "passive"))
      (node (ref "U9") (pin "35") (pinfunction "D3P_35") (pintype "input"))
    )
    (net (code "20") (name "/D4_N") (class "Default")
      (node (ref "J1") (pin "53") (pinfunction "53_53") (pintype "passive"))
      (node (ref "U9") (pin "34") (pinfunction "D4N_34") (pintype "input"))
    )
    (net (code "21") (name "/D4_P") (class "Default")
      (node (ref "J1") (pin "52") (pinfunction "52_52") (pintype "passive"))
      (node (ref "U9") (pin "33") (pinfunction "D4P_33") (pintype "input"))
    )
    (net (code "22") (name "/D5_N") (class "Default")
      (node (ref "J1") (pin "51") (pinfunction "51_51") (pintype "passive"))
      (node (ref "U9") (pin "32") (pinfunction "D5N_32") (pintype "input"))
    )
    (net (code "23") (name "/D5_P") (class "Default")
      (node (ref "J1") (pin "50") (pinfunction "50_50") (pintype "passive"))
      (node (ref "U9") (pin "31") (pinfunction "D5P_31") (pintype "input"))
    )
    (net (code "24") (name "/D6_N") (class "Default")
      (node (ref "J1") (pin "18") (pinfunction "18_18") (pintype "passive"))
      (node (ref "U9") (pin "30") (pinfunction "D6N_30") (pintype "input"))
    )
    (net (code "25") (name "/D6_P") (class "Default")
      (node (ref "J1") (pin "17") (pinfunction "17_17") (pintype "passive"))
      (node (ref "U9") (pin "29") (pinfunction "D6P_29") (pintype "input"))
    )
    (net (code "26") (name "/D7_N") (class "Default")
      (node (ref "J1") (pin "46") (pinfunction "46_46") (pintype "passive"))
      (node (ref "U9") (pin "28") (pinfunction "D7N_28") (pintype "input"))
    )
    (net (code "27") (name "/D7_P") (class "Default")
      (node (ref "J1") (pin "45") (pinfunction "45_45") (pintype "passive"))
      (node (ref "U9") (pin "27") (pinfunction "D7P_27") (pintype "input"))
    )
    (net (code "28") (name "/D8_N") (class "Default")
      (node (ref "J1") (pin "44") (pinfunction "44_44") (pintype "passive"))
      (node (ref "U9") (pin "24") (pinfunction "D8N_24") (pintype "input"))
    )
    (net (code "29") (name "/D8_P") (class "Default")
      (node (ref "J1") (pin "43") (pinfunction "43_43") (pintype "passive"))
      (node (ref "U9") (pin "23") (pinfunction "D8P_23") (pintype "input"))
    )
    (net (code "30") (name "/D9_N") (class "Default")
      (node (ref "J1") (pin "9") (pinfunction "9_9") (pintype "passive"))
      (node (ref "U9") (pin "22") (pinfunction "D9N_22") (pintype "input"))
    )
    (net (code "31") (name "/D9_P") (class "Default")
      (node (ref "J1") (pin "8") (pinfunction "8_8") (pintype "passive"))
      (node (ref "U9") (pin "21") (pinfunction "D9P_21") (pintype "input"))
    )
    (net (code "32") (name "/D10_N") (class "Default")
      (node (ref "J1") (pin "42") (pinfunction "42_42") (pintype "passive"))
      (node (ref "U9") (pin "20") (pinfunction "D10N_20") (pintype "input"))
    )
    (net (code "33") (name "/D10_P") (class "Default")
      (node (ref "J1") (pin "41") (pinfunction "41_41") (pintype "passive"))
      (node (ref "U9") (pin "19") (pinfunction "D10P_19") (pintype "input"))
    )
    (net (code "34") (name "/D11_N") (class "Default")
      (node (ref "J1") (pin "7") (pinfunction "7_7") (pintype "passive"))
      (node (ref "U9") (pin "18") (pinfunction "D11N_18") (pintype "input"))
    )
    (net (code "35") (name "/D11_P") (class "Default")
      (node (ref "J1") (pin "6") (pinfunction "6_6") (pintype "passive"))
      (node (ref "U9") (pin "17") (pinfunction "D11P_17") (pintype "input"))
    )
    (net (code "36") (name "/D12_N") (class "Default")
      (node (ref "J1") (pin "37") (pinfunction "37_37") (pintype "passive"))
      (node (ref "U9") (pin "16") (pinfunction "D12N_16") (pintype "input"))
    )
    (net (code "37") (name "/D12_P") (class "Default")
      (node (ref "J1") (pin "36") (pinfunction "36_36") (pintype "passive"))
      (node (ref "U9") (pin "15") (pinfunction "D12P_15") (pintype "input"))
    )
    (net (code "38") (name "/D13_N") (class "Default")
      (node (ref "J1") (pin "5") (pinfunction "5_5") (pintype "passive"))
      (node (ref "U9") (pin "14") (pinfunction "D13N_14") (pintype "input"))
    )
    (net (code "39") (name "/D13_P") (class "Default")
      (node (ref "J1") (pin "4") (pinfunction "4_4") (pintype "passive"))
      (node (ref "U9") (pin "13") (pinfunction "D13P_13") (pintype "input"))
    )
    (net (code "40") (name "/D14_N") (class "Default")
      (node (ref "J1") (pin "35") (pinfunction "35_35") (pintype "passive"))
      (node (ref "U9") (pin "12") (pinfunction "D14N_12") (pintype "input"))
    )
    (net (code "41") (name "/D14_P") (class "Default")
      (node (ref "J1") (pin "34") (pinfunction "34_34") (pintype "passive"))
      (node (ref "U9") (pin "11") (pinfunction "D14P_11") (pintype "input"))
    )
    (net (code "42") (name "/D15_N") (class "Default")
      (node (ref "J1") (pin "33") (pinfunction "33_33") (pintype "passive"))
      (node (ref "U9") (pin "8") (pinfunction "D15N_(MSB)_8") (pintype "input"))
    )
    (net (code "43") (name "/D15_P") (class "Default")
      (node (ref "J1") (pin "32") (pinfunction "32_32") (pintype "passive"))
      (node (ref "U9") (pin "7") (pinfunction "D15P_(MSB)_7") (pintype "input"))
    )
    (net (code "44") (name "/DAC_CLKIN_N") (class "Default")
      (node (ref "C7") (pin "2") (pinfunction "2_2") (pintype "passive"))
      (node (ref "R6") (pin "1") (pinfunction "1_1") (pintype "passive"))
      (node (ref "U9") (pin "3") (pinfunction "CLKINC_3") (pintype "input"))
    )
    (net (code "45") (name "/DAC_CLKIN_P") (class "Default")
      (node (ref "C2") (pin "2") (pinfunction "2_2") (pintype "passive"))
      (node (ref "R6") (pin "2") (pinfunction "2_2") (pintype "passive"))
      (node (ref "U9") (pin "2") (pinfunction "CLKIN_2") (pintype "input"))
    )
    (net (code "46") (name "/DCLK_IN_N") (class "Default")
      (node (ref "C105") (pin "2") (pinfunction "2_2") (pintype "passive"))
      (node (ref "J1") (pin "47") (pinfunction "47_47") (pintype "passive"))
      (node (ref "R60") (pin "1") (pinfunction "1_1") (pintype "passive"))
    )
    (net (code "47") (name "/DCLK_IN_P") (class "Default")
      (node (ref "C104") (pin "2") (pinfunction "2_2") (pintype "passive"))
      (node (ref "J1") (pin "48") (pinfunction "48_48") (pintype "passive"))
      (node (ref "R60") (pin "2") (pinfunction "2_2") (pintype "passive"))
    )
    (net (code "48") (name "/DCLK_N") (class "Default")
      (node (ref "C105") (pin "1") (pinfunction "1_1") (pintype "passive"))
      (node (ref "U9") (pin "26") (pinfunction "DCLKN_26") (pintype "input"))
    )
    (net (code "49") (name "/DCLK_P") (class "Default")
      (node (ref "C104") (pin "1") (pinfunction "1_1") (pintype "passive"))
      (node (ref "U9") (pin "25") (pinfunction "DCLKP_25") (pintype "input"))
    )
    (net (code "50") (name "/DTR") (class "Default")
      (node (ref "JP4") (pin "2") (pinfunction "2_2") (pintype "passive"))
      (node (ref "Q1") (pin "4") (pinfunction "E_4") (pintype "passive"))
      (node (ref "R38") (pin "1") (pinfunction "1_1") (pintype "passive"))
    )
    (net (code "51") (name "/D_N") (class "Default")
      (node (ref "C20") (pin "2") (pinfunction "2_2") (pintype "passive"))
      (node (ref "U1") (pin "2") (pinfunction "~{D}_2") (pintype "input"))
    )
    (net (code "52") (name "/D_P") (class "Default")
      (node (ref "C15") (pin "2") (pinfunction "2_2") (pintype "passive"))
      (node (ref "U1") (pin "1") (pinfunction "D_1") (pintype "input"))
    )
    (net (code "53") (name "/FPGA_CLKIN_N") (class "Default")
      (node (ref "J1") (pin "39") (pinfunction "39_39") (pintype "passive"))
      (node (ref "R18") (pin "2") (pinfunction "2_2") (pintype "passive"))
      (node (ref "R20") (pin "2") (pinfunction "2_2") (pintype "passive"))
    )
    (net (code "54") (name "/FPGA_CLKIN_P") (class "Default")
      (node (ref "J1") (pin "38") (pinfunction "38_38") (pintype "passive"))
      (node (ref "R14") (pin "1") (pinfunction "1_1") (pintype "passive"))
      (node (ref "R17") (pin "2") (pinfunction "2_2") (pintype "passive"))
    )
    (net (code "55") (name "/IOUTA_N") (class "Default")
      (node (ref "R46") (pin "2") (pinfunction "2_2") (pintype "passive"))
      (node (ref "R47") (pin "2") (pinfunction "2_2") (pintype "passive"))
      (node (ref "T1") (pin "1") (pinfunction "SECONDARY_DOT_1") (pintype "passive"))
      (node (ref "U9") (pin "52") (pinfunction "IOUTA1_52") (pintype "output"))
    )
    (net (code "56") (name "/IOUTA_P") (class "Default")
      (node (ref "R47") (pin "1") (pinfunction "1_1") (pintype "passive"))
      (node (ref "R50") (pin "2") (pinfunction "2_2") (pintype "passive"))
      (node (ref "T1") (pin "3") (pinfunction "SECONDARY_MID_3") (pintype "passive"))
      (node (ref "U9") (pin "53") (pinfunction "IOUTA2_53") (pintype "output"))
    )
    (net (code "57") (name "/IOUTB_N") (class "Default")
      (node (ref "R53") (pin "2") (pinfunction "2_2") (pintype "passive"))
      (node (ref "R56") (pin "2") (pinfunction "2_2") (pintype "passive"))
      (node (ref "T2") (pin "3") (pinfunction "SECONDARY_MID_3") (pintype "passive"))
      (node (ref "U9") (pin "61") (pinfunction "IOUTB1_61") (pintype "output"))
    )
    (net (code "58") (name "/IOUTB_P") (class "Default")
      (node (ref "R56") (pin "1") (pinfunction "1_1") (pintype "passive"))
      (node (ref "R57") (pin "2") (pinfunction "2_2") (pintype "passive"))
      (node (ref "T2") (pin "1") (pinfunction "SECONDARY_DOT_1") (pintype "passive"))
      (node (ref "U9") (pin "60") (pinfunction "IOUTB2_60") (pintype "output"))
    )
    (net (code "59") (name "/NRST") (class "Default")
      (node (ref "C86") (pin "1") (pinfunction "1_1") (pintype "passive"))
      (node (ref "JP4") (pin "9") (pinfunction "9_9") (pintype "passive"))
      (node (ref "Q1") (pin "6") (pinfunction "C_6") (pintype "passive"))
      (node (ref "R41") (pin "2") (pinfunction "2_2") (pintype "passive"))
      (node (ref "SW2") (pin "1") (pinfunction "1_1") (pintype "passive"))
      (node (ref "U8") (pin "10") (pinfunction "PF2/NRST_10") (pintype "bidirectional"))
    )
    (net (code "60") (name "/PA2") (class "Default")
      (node (ref "JP4") (pin "8") (pinfunction "8_8") (pintype "passive"))
      (node (ref "U8") (pin "13") (pinfunction "PA2_13") (pintype "bidirectional"))
    )
    (net (code "61") (name "/PA3") (class "Default")
      (node (ref "JP4") (pin "10") (pinfunction "10_10") (pintype "passive"))
      (node (ref "U8") (pin "14") (pinfunction "PA3_14") (pintype "bidirectional"))
    )
    (net (code "62") (name "/PA4") (class "Default")
      (node (ref "R35") (pin "1") (pinfunction "1_1") (pintype "passive"))
      (node (ref "U8") (pin "15") (pinfunction "PA4_15") (pintype "bidirectional"))
    )
    (net (code "63") (name "/PA5") (class "Default")
      (node (ref "R30") (pin "1") (pinfunction "1_1") (pintype "passive"))
      (node (ref "U8") (pin "7") (pinfunction "PA5_7") (pintype "bidirectional"))
    )
    (net (code "64") (name "/PA6") (class "Default")
      (node (ref "R29") (pin "1") (pinfunction "1_1") (pintype "passive"))
      (node (ref "U8") (pin "6") (pinfunction "PA6_6") (pintype "bidirectional"))
    )
    (net (code "65") (name "/PA7") (class "Default")
      (node (ref "R36") (pin "1") (pinfunction "1_1") (pintype "passive"))
      (node (ref "U8") (pin "16") (pinfunction "PA7_16") (pintype "bidirectional"))
    )
    (net (code "66") (name "/PB0") (class "Default")
      (node (ref "R37") (pin "1") (pinfunction "1_1") (pintype "passive"))
      (node (ref "U8") (pin "17") (pinfunction "PB0_17") (pintype "bidirectional"))
    )
    (net (code "67") (name "/PB1") (class "Default")
      (node (ref "R40") (pin "1") (pinfunction "1_1") (pintype "passive"))
      (node (ref "U8") (pin "19") (pinfunction "PB1_19") (pintype "bidirectional"))
    )
    (net (code "68") (name "/PB2") (class "Default")
      (node (ref "R39") (pin "1") (pinfunction "1_1") (pintype "passive"))
      (node (ref "U8") (pin "18") (pinfunction "PB2_18") (pintype "bidirectional"))
    )
    (net (code "69") (name "/PB3") (class "Default")
      (node (ref "R42") (pin "1") (pinfunction "1_1") (pintype "passive"))
      (node (ref "U8") (pin "4") (pinfunction "PB3_4") (pintype "bidirectional"))
    )
    (net (code "70") (name "/PF0") (class "Default")
      (node (ref "R33") (pin "1") (pinfunction "1_1") (pintype "passive"))
      (node (ref "U8") (pin "8") (pinfunction "PF0/OSCIN_8") (pintype "bidirectional"))
    )
    (net (code "71") (name "/PF1") (class "Default")
      (node (ref "R34") (pin "1") (pinfunction "1_1") (pintype "passive"))
      (node (ref "U8") (pin "9") (pinfunction "PF1/OSCOUT_9") (pintype "bidirectional"))
    )
    (net (code "72") (name "/PG") (class "Default")
      (node (ref "R9") (pin "1") (pinfunction "1_1") (pintype "passive"))
      (node (ref "U3") (pin "8") (pinfunction "PG_8") (pintype "output"))
    )
    (net (code "73") (name "/Q1_N") (class "Default")
      (node (ref "R10") (pin "2") (pinfunction "2_2") (pintype "passive"))
      (node (ref "R11") (pin "2") (pinfunction "2_2") (pintype "passive"))
      (node (ref "R8") (pin "1") (pinfunction "1_1") (pintype "passive"))
      (node (ref "U1") (pin "11") (pinfunction "~{Q1}_11") (pintype "output"))
    )
    (net (code "74") (name "/Q1_P") (class "Default")
      (node (ref "R1") (pin "1") (pinfunction "1_1") (pintype "passive"))
      (node (ref "R2") (pin "1") (pinfunction "1_1") (pintype "passive"))
      (node (ref "R3") (pin "1") (pinfunction "1_1") (pintype "passive"))
      (node (ref "U1") (pin "12") (pinfunction "Q1_12") (pintype "output"))
    )
    (net (code "75") (name "/Q2_N") (class "Default")
      (node (ref "R18") (pin "1") (pinfunction "1_1") (pintype "passive"))
      (node (ref "R19") (pin "2") (pinfunction "2_2") (pintype "passive"))
      (node (ref "U1") (pin "9") (pinfunction "~{Q2}_9") (pintype "output"))
    )
    (net (code "76") (name "/Q2_P") (class "Default")
      (node (ref "R13") (pin "1") (pinfunction "1_1") (pintype "passive"))
      (node (ref "R17") (pin "1") (pinfunction "1_1") (pintype "passive"))
      (node (ref "U1") (pin "10") (pinfunction "Q2_10") (pintype "output"))
    )
    (net (code "77") (name "/RESETB_DAC") (class "Default")
      (node (ref "R35") (pin "2") (pinfunction "2_2") (pintype "passive"))
      (node (ref "U9") (pin "49") (pinfunction "RESETB_49") (pintype "input"))
    )
    (net (code "78") (name "/RTS") (class "Default")
      (node (ref "JP4") (pin "4") (pinfunction "4_4") (pintype "passive"))
      (node (ref "Q1") (pin "1") (pinfunction "E_1") (pintype "passive"))
      (node (ref "R43") (pin "1") (pinfunction "1_1") (pintype "passive"))
    )
    (net (code "79") (name "/SCK_PLL") (class "Default")
      (node (ref "R30") (pin "2") (pinfunction "2_2") (pintype "passive"))
      (node (ref "U2") (pin "32") (pinfunction "SCK_32") (pintype "input"))
    )
    (net (code "80") (name "/SCLK_DAC") (class "Default")
      (node (ref "R37") (pin "2") (pinfunction "2_2") (pintype "passive"))
      (node (ref "U9") (pin "47") (pinfunction "SCLK_47") (pintype "input"))
    )
    (net (code "81") (name "/SDENB_DAC") (class "Default")
      (node (ref "R36") (pin "2") (pinfunction "2_2") (pintype "passive"))
      (node (ref "U9") (pin "48") (pinfunction "SDENB_48") (pintype "input"))
    )
    (net (code "82") (name "/SDIO_DAC") (class "Default")
      (node (ref "R39") (pin "2") (pinfunction "2_2") (pintype "passive"))
      (node (ref "U9") (pin "46") (pinfunction "SDIO_46") (pintype "bidirectional"))
    )
    (net (code "83") (name "/SDI_PLL") (class "Default")
      (node (ref "R29") (pin "2") (pinfunction "2_2") (pintype "passive"))
      (node (ref "U2") (pin "31") (pinfunction "SDI_31") (pintype "input"))
    )
    (net (code "84") (name "/SDO_DAC") (class "Default")
      (node (ref "R40") (pin "2") (pinfunction "2_2") (pintype "passive"))
      (node (ref "U9") (pin "45") (pinfunction "SDO_45") (pintype "tri_state"))
    )
    (net (code "85") (name "/SDO_PLL") (class "Default")
      (node (ref "R33") (pin "2") (pinfunction "2_2") (pintype "passive"))
      (node (ref "U2") (pin "33") (pinfunction "LD/SDO_33") (pintype "output"))
    )
    (net (code "86") (name "/SEN_PLL") (class "Default")
      (node (ref "R34") (pin "2") (pinfunction "2_2") (pintype "passive"))
      (node (ref "U2") (pin "30") (pinfunction "SEN_30") (pintype "input"))
    )
    (net (code "87") (name "/SWC") (class "Default")
      (node (ref "JP4") (pin "5") (pinfunction "5_5") (pintype "passive"))
      (node (ref "U8") (pin "3") (pinfunction "PA14/SWC_3") (pintype "bidirectional"))
    )
    (net (code "88") (name "/SWD") (class "Default")
      (node (ref "JP4") (pin "3") (pinfunction "3_3") (pintype "passive"))
      (node (ref "U8") (pin "2") (pinfunction "PA13/SWD_2") (pintype "bidirectional"))
    )
    (net (code "89") (name "/SYNC_N") (class "Default")
      (node (ref "J1") (pin "3") (pinfunction "3_3") (pintype "passive"))
      (node (ref "U9") (pin "6") (pinfunction "SYNCN_6") (pintype "input"))
    )
    (net (code "90") (name "/SYNC_P") (class "Default")
      (node (ref "J1") (pin "2") (pinfunction "2_2") (pintype "passive"))
      (node (ref "U9") (pin "5") (pinfunction "SYNCP_5") (pintype "input"))
    )
    (net (code "91") (name "/UART_RX") (class "Default")
      (node (ref "JP5") (pin "2") (pinfunction "2_2") (pintype "passive"))
      (node (ref "U8") (pin "12") (pinfunction "PA1_12") (pintype "bidirectional"))
    )
    (net (code "92") (name "/UART_TX") (class "Default")
      (node (ref "JP5") (pin "3") (pinfunction "3_3") (pintype "passive"))
      (node (ref "U8") (pin "11") (pinfunction "PA0_11") (pintype "bidirectional"))
    )
    (net (code "93") (name "/VTUNE") (class "Default")
      (node (ref "C6") (pin "2") (pinfunction "2_2") (pintype "passive"))
      (node (ref "R5") (pin "1") (pinfunction "1_1") (pintype "passive"))
      (node (ref "U2") (pin "23") (pinfunction "VTUNE_23") (pintype "input"))
    )
    (net (code "94") (name "/XREF") (class "Default")
      (node (ref "C16") (pin "1") (pinfunction "1_1") (pintype "passive"))
      (node (ref "U2") (pin "15") (pinfunction "XREFP_15") (pintype "input"))
    )
    (net (code "95") (name "GND") (class "Default")
      (node (ref "C1") (pin "2") (pinfunction "2_2") (pintype "passive"))
      (node (ref "C10") (pin "1") (pinfunction "1_1") (pintype "passive"))
      (node (ref "C100") (pin "1") (pinfunction "1_1") (pintype "passive"))
      (node (ref "C101") (pin "1") (pinfunction "1_1") (pintype "passive"))
      (node (ref "C102") (pin "1") (pinfunction "1_1") (pintype "passive"))
      (node (ref "C103") (pin "1") (pinfunction "1_1") (pintype "passive"))
      (node (ref "C106") (pin "1") (pinfunction "1_1") (pintype "passive"))
      (node (ref "C11") (pin "1") (pinfunction "1_1") (pintype "passive"))
      (node (ref "C12") (pin "1") (pinfunction "1_1") (pintype "passive"))
      (node (ref "C13") (pin "1") (pinfunction "1_1") (pintype "passive"))
      (node (ref "C14") (pin "1") (pinfunction "1_1") (pintype "passive"))
      (node (ref "C17") (pin "1") (pinfunction "1_1") (pintype "passive"))
      (node (ref "C18") (pin "1") (pinfunction "1_1") (pintype "passive"))
      (node (ref "C19") (pin "1") (pinfunction "1_1") (pintype "passive"))
      (node (ref "C21") (pin "1") (pinfunction "1_1") (pintype "passive"))
      (node (ref "C22") (pin "1") (pinfunction "1_1") (pintype "passive"))
      (node (ref "C23") (pin "2") (pinfunction "2_2") (pintype "passive"))
      (node (ref "C24") (pin "2") (pinfunction "2_2") (pintype "passive"))
      (node (ref "C25") (pin "1") (pinfunction "1_1") (pintype "passive"))
      (node (ref "C26") (pin "1") (pinfunction "1_1") (pintype "passive"))
      (node (ref "C27") (pin "1") (pinfunction "1_1") (pintype "passive"))
      (node (ref "C28") (pin "1") (pinfunction "1_1") (pintype "passive"))
      (node (ref "C29") (pin "1") (pinfunction "1_1") (pintype "passive"))
      (node (ref "C30") (pin "1") (pinfunction "1_1") (pintype "passive"))
      (node (ref "C31") (pin "1") (pinfunction "1_1") (pintype "passive"))
      (node (ref "C32") (pin "1") (pinfunction "1_1") (pintype "passive"))
      (node (ref "C33") (pin "1") (pinfunction "1_1") (pintype "passive"))
      (node (ref "C34") (pin "1") (pinfunction "1_1") (pintype "passive"))
      (node (ref "C35") (pin "1") (pinfunction "1_1") (pintype "passive"))
      (node (ref "C36") (pin "1") (pinfunction "1_1") (pintype "passive"))
      (node (ref "C37") (pin "1") (pinfunction "1_1") (pintype "passive"))
      (node (ref "C38") (pin "1") (pinfunction "1_1") (pintype "passive"))
      (node (ref "C39") (pin "1") (pinfunction "1_1") (pintype "passive"))
      (node (ref "C4") (pin "1") (pinfunction "1_1") (pintype "passive"))
      (node (ref "C40") (pin "1") (pinfunction "1_1") (pintype "passive"))
      (node (ref "C41") (pin "1") (pinfunction "1_1") (pintype "passive"))
      (node (ref "C42") (pin "1") (pinfunction "1_1") (pintype "passive"))
      (node (ref "C43") (pin "1") (pinfunction "1_1") (pintype "passive"))
      (node (ref "C44") (pin "1") (pinfunction "1_1") (pintype "passive"))
      (node (ref "C45") (pin "1") (pinfunction "1_1") (pintype "passive"))
      (node (ref "C46") (pin "1") (pinfunction "1_1") (pintype "passive"))
      (node (ref "C47") (pin "1") (pinfunction "1_1") (pintype "passive"))
      (node (ref "C48") (pin "2") (pinfunction "2_2") (pintype "passive"))
      (node (ref "C49") (pin "2") (pinfunction "2_2") (pintype "passive"))
      (node (ref "C5") (pin "1") (pinfunction "1_1") (pintype "passive"))
      (node (ref "C50") (pin "2") (pinfunction "2_2") (pintype "passive"))
      (node (ref "C51") (pin "2") (pinfunction "2_2") (pintype "passive"))
      (node (ref "C52") (pin "1") (pinfunction "1_1") (pintype "passive"))
      (node (ref "C53") (pin "1") (pinfunction "1_1") (pintype "passive"))
      (node (ref "C54") (pin "1") (pinfunction "1_1") (pintype "passive"))
      (node (ref "C55") (pin "1") (pinfunction "1_1") (pintype "passive"))
      (node (ref "C56") (pin "2") (pinfunction "2_2") (pintype "passive"))
      (node (ref "C57") (pin "1") (pinfunction "1_1") (pintype "passive"))
      (node (ref "C58") (pin "1") (pinfunction "1_1") (pintype "passive"))
      (node (ref "C59") (pin "1") (pinfunction "1_1") (pintype "passive"))
      (node (ref "C6") (pin "1") (pinfunction "1_1") (pintype "passive"))
      (node (ref "C60") (pin "1") (pinfunction "1_1") (pintype "passive"))
      (node (ref "C61") (pin "1") (pinfunction "1_1") (pintype "passive"))
      (node (ref "C62") (pin "1") (pinfunction "1_1") (pintype "passive"))
      (node (ref "C63") (pin "1") (pinfunction "1_1") (pintype "passive"))
      (node (ref "C64") (pin "1") (pinfunction "1_1") (pintype "passive"))
      (node (ref "C65") (pin "1") (pinfunction "1_1") (pintype "passive"))
      (node (ref "C66") (pin "1") (pinfunction "1_1") (pintype "passive"))
      (node (ref "C67") (pin "1") (pinfunction "1_1") (pintype "passive"))
      (node (ref "C68") (pin "1") (pinfunction "1_1") (pintype "passive"))
      (node (ref "C69") (pin "1") (pinfunction "1_1") (pintype "passive"))
      (node (ref "C70") (pin "1") (pinfunction "1_1") (pintype "passive"))
      (node (ref "C71") (pin "1") (pinfunction "1_1") (pintype "passive"))
      (node (ref "C72") (pin "1") (pinfunction "1_1") (pintype "passive"))
      (node (ref "C73") (pin "1") (pinfunction "1_1") (pintype "passive"))
      (node (ref "C74") (pin "1") (pinfunction "1_1") (pintype "passive"))
      (node (ref "C75") (pin "1") (pinfunction "1_1") (pintype "passive"))
      (node (ref "C76") (pin "1") (pinfunction "1_1") (pintype "passive"))
      (node (ref "C77") (pin "1") (pinfunction "1_1") (pintype "passive"))
      (node (ref "C78") (pin "1") (pinfunction "1_1") (pintype "passive"))
      (node (ref "C79") (pin "1") (pinfunction "1_1") (pintype "passive"))
      (node (ref "C8") (pin "1") (pinfunction "1_1") (pintype "passive"))
      (node (ref "C80") (pin "1") (pinfunction "1_1") (pintype "passive"))
      (node (ref "C81") (pin "1") (pinfunction "1_1") (pintype "passive"))
      (node (ref "C82") (pin "1") (pinfunction "1_1") (pintype "passive"))
      (node (ref "C83") (pin "1") (pinfunction "1_1") (pintype "passive"))
      (node (ref "C84") (pin "1") (pinfunction "1_1") (pintype "passive"))
      (node (ref "C85") (pin "1") (pinfunction "1_1") (pintype "passive"))
      (node (ref "C86") (pin "2") (pinfunction "2_2") (pintype "passive"))
      (node (ref "C89") (pin "2") (pinfunction "2_2") (pintype "passive"))
      (node (ref "C9") (pin "1") (pinfunction "1_1") (pintype "passive"))
      (node (ref "C90") (pin "2") (pinfunction "2_2") (pintype "passive"))
      (node (ref "C93") (pin "2") (pinfunction "2_2") (pintype "passive"))
      (node (ref "C94") (pin "2") (pinfunction "2_2") (pintype "passive"))
      (node (ref "C95") (pin "2") (pinfunction "2_2") (pintype "passive"))
      (node (ref "C96") (pin "1") (pinfunction "1_1") (pintype "passive"))
      (node (ref "C97") (pin "1") (pinfunction "1_1") (pintype "passive"))
      (node (ref "C98") (pin "1") (pinfunction "1_1") (pintype "passive"))
      (node (ref "C99") (pin "1") (pinfunction "1_1") (pintype "passive"))
      (node (ref "FL1") (pin "2") (pinfunction "GND_2") (pintype "power_in"))
      (node (ref "FL2") (pin "2") (pinfunction "GND_2") (pintype "power_in"))
      (node (ref "J1") (pin "1") (pinfunction "1_1") (pintype "passive"))
      (node (ref "J1") (pin "10") (pinfunction "10_10") (pintype "passive"))
      (node (ref "J1") (pin "19") (pinfunction "19_19") (pintype "passive"))
      (node (ref "J1") (pin "28") (pinfunction "28_28") (pintype "passive"))
      (node (ref "J1") (pin "31") (pinfunction "31_31") (pintype "passive"))
      (node (ref "J1") (pin "40") (pinfunction "40_40") (pintype "passive"))
      (node (ref "J1") (pin "49") (pinfunction "49_49") (pintype "passive"))
      (node (ref "J1") (pin "58") (pinfunction "58_58") (pintype "passive"))
      (node (ref "J2") (pin "2") (pinfunction "2_2") (pintype "passive"))
      (node (ref "J2") (pin "3") (pinfunction "3_3") (pintype "passive"))
      (node (ref "J2") (pin "4") (pinfunction "4_4") (pintype "passive"))
      (node (ref "J3") (pin "2") (pinfunction "2_2") (pintype "passive"))
      (node (ref "J3") (pin "3") (pinfunction "3_3") (pintype "passive"))
      (node (ref "J3") (pin "4") (pinfunction "4_4") (pintype "passive"))
      (node (ref "JP1") (pin "1") (pinfunction "1_1") (pintype "passive"))
      (node (ref "JP2") (pin "1") (pinfunction "1_1") (pintype "passive"))
      (node (ref "JP3") (pin "1") (pinfunction "1_1") (pintype "passive"))
      (node (ref "JP4") (pin "1") (pinfunction "1_1") (pintype "passive"))
      (node (ref "JP4") (pin "6") (pinfunction "6_6") (pintype "passive"))
      (node (ref "JP5") (pin "1") (pinfunction "1_1") (pintype "passive"))
      (node (ref "LED2") (pin "2") (pinfunction "K_2") (pintype "passive"))
      (node (ref "R11") (pin "1") (pinfunction "1_1") (pintype "passive"))
      (node (ref "R14") (pin "2") (pinfunction "2_2") (pintype "passive"))
      (node (ref "R15") (pin "2") (pinfunction "2_2") (pintype "passive"))
      (node (ref "R16") (pin "2") (pinfunction "2_2") (pintype "passive"))
      (node (ref "R2") (pin "2") (pinfunction "2_2") (pintype "passive"))
      (node (ref "R20") (pin "1") (pinfunction "1_1") (pintype "passive"))
      (node (ref "R24") (pin "2") (pinfunction "2_2") (pintype "passive"))
      (node (ref "R25") (pin "1") (pinfunction "1_1") (pintype "passive"))
      (node (ref "R31") (pin "2") (pinfunction "2_2") (pintype "passive"))
      (node (ref "R32") (pin "1") (pinfunction "1_1") (pintype "passive"))
      (node (ref "R45") (pin "1") (pinfunction "1_1") (pintype "passive"))
      (node (ref "R46") (pin "1") (pinfunction "1_1") (pintype "passive"))
      (node (ref "R49") (pin "2") (pinfunction "2_2") (pintype "passive"))
      (node (ref "R50") (pin "1") (pinfunction "1_1") (pintype "passive"))
      (node (ref "R51") (pin "1") (pinfunction "1_1") (pintype "passive"))
      (node (ref "R53") (pin "1") (pinfunction "1_1") (pintype "passive"))
      (node (ref "R55") (pin "2") (pinfunction "2_2") (pintype "passive"))
      (node (ref "R57") (pin "1") (pinfunction "1_1") (pintype "passive"))
      (node (ref "R58") (pin "1") (pinfunction "1_1") (pintype "passive"))
      (node (ref "R61") (pin "2") (pinfunction "2_2") (pintype "passive"))
      (node (ref "SW2") (pin "2") (pinfunction "2_2") (pintype "passive"))
      (node (ref "T1") (pin "4") (pinfunction "PRIMARY_4") (pintype "passive"))
      (node (ref "T2") (pin "6") (pinfunction "PRIMARY_DOT_6") (pintype "passive"))
      (node (ref "U1") (pin "14") (pinfunction "VEE_14") (pintype "power_in"))
      (node (ref "U1") (pin "17") (pinfunction "EP_17") (pintype "passive"))
      (node (ref "U1") (pin "3") (pinfunction "NC_3") (pintype "passive"))
      (node (ref "U1") (pin "4") (pinfunction "NC_4") (pintype "passive"))
      (node (ref "U1") (pin "5") (pinfunction "NC_5") (pintype "passive"))
      (node (ref "U1") (pin "6") (pinfunction "NC_6") (pintype "passive"))
      (node (ref "U1") (pin "7") (pinfunction "VEE_7") (pintype "power_in"))
      (node (ref "U10") (pin "2") (pinfunction "-Vs_2") (pintype "power_in"))
      (node (ref "U11") (pin "2") (pinfunction "-Vs_2") (pintype "power_in"))
      (node (ref "U2") (pin "11") (pinfunction "NC_11") (pintype "passive"))
      (node (ref "U2") (pin "12") (pinfunction "NC_12") (pintype "passive"))
      (node (ref "U2") (pin "13") (pinfunction "NC_13") (pintype "passive"))
      (node (ref "U2") (pin "14") (pinfunction "NC_14") (pintype "passive"))
      (node (ref "U2") (pin "18") (pinfunction "NC_18") (pintype "passive"))
      (node (ref "U2") (pin "19") (pinfunction "NC_19") (pintype "passive"))
      (node (ref "U2") (pin "2") (pinfunction "NC_2") (pintype "passive"))
      (node (ref "U2") (pin "20") (pinfunction "NC_20") (pintype "passive"))
      (node (ref "U2") (pin "21") (pinfunction "NC_21") (pintype "passive"))
      (node (ref "U2") (pin "22") (pinfunction "NC_22") (pintype "passive"))
      (node (ref "U2") (pin "24") (pinfunction "NC_24") (pintype "passive"))
      (node (ref "U2") (pin "26") (pinfunction "NC_26") (pintype "passive"))
      (node (ref "U2") (pin "34") (pinfunction "NC_34") (pintype "passive"))
      (node (ref "U2") (pin "37") (pinfunction "NC_37") (pintype "passive"))
      (node (ref "U2") (pin "38") (pinfunction "NC_38") (pintype "passive"))
      (node (ref "U2") (pin "41") (pinfunction "EP_41") (pintype "power_in"))
      (node (ref "U2") (pin "5") (pinfunction "NC_5") (pintype "passive"))
      (node (ref "U2") (pin "6") (pinfunction "NC_6") (pintype "passive"))
      (node (ref "U2") (pin "8") (pinfunction "NC_8") (pintype "passive"))
      (node (ref "U2") (pin "9") (pinfunction "NC_9") (pintype "passive"))
      (node (ref "U3") (pin "1") (pinfunction "PGND_1") (pintype "power_in"))
      (node (ref "U3") (pin "11") (pinfunction "AGND_11") (pintype "power_in"))
      (node (ref "U3") (pin "2") (pinfunction "PGND_2") (pintype "power_in"))
      (node (ref "U4") (pin "2") (pinfunction "GND_2") (pintype "power_in"))
      (node (ref "U5") (pin "4") (pinfunction "GND_4") (pintype "power_in"))
      (node (ref "U5") (pin "9") (pinfunction "GND_9") (pintype "power_in"))
      (node (ref "U6") (pin "2") (pinfunction "GND_2") (pintype "power_in"))
      (node (ref "U7") (pin "4") (pinfunction "GND_4") (pintype "power_in"))
      (node (ref "U7") (pin "9") (pinfunction "GND_9") (pintype "power_in"))
      (node (ref "U8") (pin "1") (pinfunction "VSS_1") (pintype "power_in"))
      (node (ref "U9") (pin "4") (pinfunction "GND_4") (pintype "power_in"))
      (node (ref "U9") (pin "58") (pinfunction "EXTLO_58") (pintype "passive"))
      (node (ref "U9") (pin "65") (pinfunction "EP_65") (pintype "power_in"))
      (node (ref "X1") (pin "2") (pinfunction "GND_2") (pintype "passive"))
    )
    (net (code "96") (name "NC") (class "Default")
      (node (ref "U3") (pin "3") (pinfunction "NC_3") (pintype "passive"))
      (node (ref "U3") (pin "4") (pinfunction "NC_4") (pintype "passive"))
    )
    (net (code "97") (name "Net-(C2-Pad1)") (class "Default")
      (node (ref "C2") (pin "1") (pinfunction "1_1") (pintype "passive"))
      (node (ref "R3") (pin "2") (pinfunction "2_2") (pintype "passive"))
    )
    (net (code "98") (name "Net-(C5-Pad2)") (class "Default")
      (node (ref "C5") (pin "2") (pinfunction "2_2") (pintype "passive"))
      (node (ref "R4") (pin "1") (pinfunction "1_1") (pintype "passive"))
      (node (ref "R5") (pin "2") (pinfunction "2_2") (pintype "passive"))
    )
    (net (code "99") (name "Net-(C7-Pad1)") (class "Default")
      (node (ref "C7") (pin "1") (pinfunction "1_1") (pintype "passive"))
      (node (ref "R8") (pin "2") (pinfunction "2_2") (pintype "passive"))
    )
    (net (code "100") (name "Net-(C14-Pad2)") (class "Default")
      (node (ref "C14") (pin "2") (pinfunction "2_2") (pintype "passive"))
      (node (ref "R7") (pin "1") (pinfunction "1_1") (pintype "passive"))
    )
    (net (code "101") (name "Net-(C87-Pad2)") (class "Default")
      (node (ref "C87") (pin "2") (pinfunction "2_2") (pintype "passive"))
      (node (ref "C90") (pin "1") (pinfunction "1_1") (pintype "passive"))
      (node (ref "L3") (pin "2") (pinfunction "2_2") (pintype "passive"))
      (node (ref "R51") (pin "2") (pinfunction "2_2") (pintype "passive"))
    )
    (net (code "102") (name "Net-(C88-Pad1)") (class "Default")
      (node (ref "C88") (pin "1") (pinfunction "1_1") (pintype "passive"))
      (node (ref "R52") (pin "2") (pinfunction "2_2") (pintype "passive"))
    )
    (net (code "103") (name "Net-(C91-Pad2)") (class "Default")
      (node (ref "C91") (pin "2") (pinfunction "2_2") (pintype "passive"))
      (node (ref "C94") (pin "1") (pinfunction "1_1") (pintype "passive"))
      (node (ref "L4") (pin "2") (pinfunction "2_2") (pintype "passive"))
      (node (ref "R58") (pin "2") (pinfunction "2_2") (pintype "passive"))
    )
    (net (code "104") (name "Net-(C92-Pad1)") (class "Default")
      (node (ref "C92") (pin "1") (pinfunction "1_1") (pintype "passive"))
      (node (ref "R59") (pin "2") (pinfunction "2_2") (pintype "passive"))
    )
    (net (code "105") (name "Net-(FL1-IN)") (class "Default")
      (node (ref "FL1") (pin "1") (pinfunction "IN_1") (pintype "passive"))
      (node (ref "R23") (pin "2") (pinfunction "2_2") (pintype "passive"))
      (node (ref "U5") (pin "1") (pinfunction "OUT_1") (pintype "power_in"))
      (node (ref "U5") (pin "2") (pinfunction "OUT_2") (pintype "power_in"))
    )
    (net (code "106") (name "Net-(FL2-IN)") (class "Default")
      (node (ref "FL2") (pin "1") (pinfunction "IN_1") (pintype "passive"))
      (node (ref "R28") (pin "2") (pinfunction "2_2") (pintype "passive"))
      (node (ref "U7") (pin "1") (pinfunction "OUT_1") (pintype "power_in"))
      (node (ref "U7") (pin "2") (pinfunction "OUT_2") (pintype "power_in"))
    )
    (net (code "107") (name "Net-(J2-Pad1)") (class "Default")
      (node (ref "J2") (pin "1") (pinfunction "1_1") (pintype "passive"))
      (node (ref "R52") (pin "1") (pinfunction "1_1") (pintype "passive"))
    )
    (net (code "108") (name "Net-(J3-Pad1)") (class "Default")
      (node (ref "J3") (pin "1") (pinfunction "1_1") (pintype "passive"))
      (node (ref "R59") (pin "1") (pinfunction "1_1") (pintype "passive"))
    )
    (net (code "109") (name "Net-(LED1-K)") (class "Default")
      (node (ref "LED1") (pin "2") (pinfunction "K_2") (pintype "passive"))
      (node (ref "R9") (pin "2") (pinfunction "2_2") (pintype "passive"))
    )
    (net (code "110") (name "Net-(LED2-A)") (class "Default")
      (node (ref "LED2") (pin "1") (pinfunction "A_1") (pintype "passive"))
      (node (ref "R42") (pin "2") (pinfunction "2_2") (pintype "passive"))
    )
    (net (code "111") (name "Net-(Q1A-B)") (class "Default")
      (node (ref "Q1") (pin "2") (pinfunction "B_2") (pintype "passive"))
      (node (ref "R38") (pin "2") (pinfunction "2_2") (pintype "passive"))
    )
    (net (code "112") (name "Net-(Q1B-B)") (class "Default")
      (node (ref "Q1") (pin "5") (pinfunction "B_5") (pintype "passive"))
      (node (ref "R43") (pin "2") (pinfunction "2_2") (pintype "passive"))
    )
    (net (code "113") (name "Net-(Q1B-C)") (class "Default")
      (node (ref "Q1") (pin "3") (pinfunction "C_3") (pintype "passive"))
      (node (ref "R44") (pin "1") (pinfunction "1_1") (pintype "passive"))
    )
    (net (code "114") (name "Net-(Q2-B)") (class "Default")
      (node (ref "Q2") (pin "1") (pinfunction "B_1") (pintype "passive"))
      (node (ref "R44") (pin "2") (pinfunction "2_2") (pintype "passive"))
    )
    (net (code "115") (name "Net-(T1-PRIMARY_DOT)") (class "Default")
      (node (ref "C89") (pin "1") (pinfunction "1_1") (pintype "passive"))
      (node (ref "L3") (pin "1") (pinfunction "1_1") (pintype "passive"))
      (node (ref "T1") (pin "6") (pinfunction "PRIMARY_DOT_6") (pintype "passive"))
    )
    (net (code "116") (name "Net-(T2-PRIMARY)") (class "Default")
      (node (ref "C93") (pin "1") (pinfunction "1_1") (pintype "passive"))
      (node (ref "L4") (pin "1") (pinfunction "1_1") (pintype "passive"))
      (node (ref "T2") (pin "4") (pinfunction "PRIMARY_4") (pintype "passive"))
    )
    (net (code "117") (name "Net-(U1-VREF)") (class "Default")
      (node (ref "C1") (pin "1") (pinfunction "1_1") (pintype "passive"))
      (node (ref "U1") (pin "15") (pinfunction "VREF_15") (pintype "power_in"))
      (node (ref "U1") (pin "16") (pinfunction "VT_16") (pintype "passive"))
    )
    (net (code "118") (name "Net-(U2A-BIAS)") (class "Default")
      (node (ref "C3") (pin "2") (pinfunction "2_2") (pintype "passive"))
      (node (ref "U2") (pin "40") (pinfunction "BIAS_40") (pintype "passive"))
    )
    (net (code "119") (name "Net-(U3-FB)") (class "Default")
      (node (ref "R12") (pin "1") (pinfunction "1_1") (pintype "passive"))
      (node (ref "R16") (pin "1") (pinfunction "1_1") (pintype "passive"))
      (node (ref "U3") (pin "10") (pinfunction "FB_10") (pintype "passive"))
    )
    (net (code "120") (name "Net-(U4-EN)") (class "Default")
      (node (ref "R22") (pin "2") (pinfunction "2_2") (pintype "passive"))
      (node (ref "U4") (pin "1") (pinfunction "EN_1") (pintype "input"))
    )
    (net (code "121") (name "Net-(U4-FB)") (class "Default")
      (node (ref "R21") (pin "2") (pinfunction "2_2") (pintype "passive"))
      (node (ref "R24") (pin "1") (pinfunction "1_1") (pintype "passive"))
      (node (ref "U4") (pin "5") (pinfunction "FB_5") (pintype "input"))
    )
    (net (code "122") (name "Net-(U4-SW)") (class "Default")
      (node (ref "L1") (pin "1") (pinfunction "1_1") (pintype "passive"))
      (node (ref "U4") (pin "3") (pinfunction "SW_3") (pintype "passive"))
    )
    (net (code "123") (name "Net-(U5-FB)") (class "Default")
      (node (ref "R23") (pin "1") (pinfunction "1_1") (pintype "passive"))
      (node (ref "R25") (pin "2") (pinfunction "2_2") (pintype "passive"))
      (node (ref "U5") (pin "3") (pinfunction "FB_3") (pintype "input"))
    )
    (net (code "124") (name "Net-(U5-NR)") (class "Default")
      (node (ref "C48") (pin "1") (pinfunction "1_1") (pintype "passive"))
      (node (ref "U5") (pin "6") (pinfunction "NR_6") (pintype "passive"))
    )
    (net (code "125") (name "Net-(U6-EN)") (class "Default")
      (node (ref "R27") (pin "2") (pinfunction "2_2") (pintype "passive"))
      (node (ref "U6") (pin "1") (pinfunction "EN_1") (pintype "input"))
    )
    (net (code "126") (name "Net-(U6-FB)") (class "Default")
      (node (ref "R26") (pin "2") (pinfunction "2_2") (pintype "passive"))
      (node (ref "R31") (pin "1") (pinfunction "1_1") (pintype "passive"))
      (node (ref "U6") (pin "5") (pinfunction "FB_5") (pintype "input"))
    )
    (net (code "127") (name "Net-(U6-SW)") (class "Default")
      (node (ref "L2") (pin "1") (pinfunction "1_1") (pintype "passive"))
      (node (ref "U6") (pin "3") (pinfunction "SW_3") (pintype "passive"))
    )
    (net (code "128") (name "Net-(U7-FB)") (class "Default")
      (node (ref "R28") (pin "1") (pinfunction "1_1") (pintype "passive"))
      (node (ref "R32") (pin "2") (pinfunction "2_2") (pintype "passive"))
      (node (ref "U7") (pin "3") (pinfunction "FB_3") (pintype "input"))
    )
    (net (code "129") (name "Net-(U7-NR)") (class "Default")
      (node (ref "C56") (pin "1") (pinfunction "1_1") (pintype "passive"))
      (node (ref "U7") (pin "6") (pinfunction "NR_6") (pintype "passive"))
    )
    (net (code "130") (name "Net-(U9A-BIASJ)") (class "Default")
      (node (ref "R61") (pin "1") (pinfunction "1_1") (pintype "passive"))
      (node (ref "U9") (pin "57") (pinfunction "BIASJ_57") (pintype "passive"))
    )
    (net (code "131") (name "Net-(U9A-EXTIO)") (class "Default")
      (node (ref "C95") (pin "1") (pinfunction "1_1") (pintype "passive"))
      (node (ref "U9") (pin "56") (pinfunction "EXTIO_56") (pintype "bidirectional"))
    )
    (net (code "132") (name "Net-(U10-+In)") (class "Default")
      (node (ref "C87") (pin "1") (pinfunction "1_1") (pintype "passive"))
      (node (ref "R48") (pin "1") (pinfunction "1_1") (pintype "passive"))
      (node (ref "R49") (pin "1") (pinfunction "1_1") (pintype "passive"))
      (node (ref "U10") (pin "3") (pinfunction "+In_3") (pintype "input"))
    )
    (net (code "133") (name "Net-(U10--In)") (class "Default")
      (node (ref "C88") (pin "2") (pinfunction "2_2") (pintype "passive"))
      (node (ref "U10") (pin "1") (pinfunction "OUT_1") (pintype "output"))
      (node (ref "U10") (pin "4") (pinfunction "-In_4") (pintype "input"))
    )
    (net (code "134") (name "Net-(U11-+In)") (class "Default")
      (node (ref "C91") (pin "1") (pinfunction "1_1") (pintype "passive"))
      (node (ref "R54") (pin "1") (pinfunction "1_1") (pintype "passive"))
      (node (ref "R55") (pin "1") (pinfunction "1_1") (pintype "passive"))
      (node (ref "U11") (pin "3") (pinfunction "+In_3") (pintype "input"))
    )
    (net (code "135") (name "Net-(U11--In)") (class "Default")
      (node (ref "C92") (pin "2") (pinfunction "2_2") (pintype "passive"))
      (node (ref "U11") (pin "1") (pinfunction "OUT_1") (pintype "output"))
      (node (ref "U11") (pin "4") (pinfunction "-In_4") (pintype "input"))
    )
    (net (code "136") (name "Net-(X1-OUT)") (class "Default")
      (node (ref "C16") (pin "2") (pinfunction "2_2") (pintype "passive"))
      (node (ref "R15") (pin "1") (pinfunction "1_1") (pintype "passive"))
      (node (ref "X1") (pin "3") (pinfunction "OUT_3") (pintype "passive"))
    )
    (net (code "137") (name "Net-(X1-VCC)") (class "Default")
      (node (ref "FB1") (pin "2") (pinfunction "2_2") (pintype "passive"))
      (node (ref "X1") (pin "4") (pinfunction "VCC_4") (pintype "passive"))
    )
    (net (code "138") (name "unconnected-(J1-Pad11)") (class "Default")
      (node (ref "J1") (pin "11") (pinfunction "11_11") (pintype "passive+no_connect"))
    )
    (net (code "139") (name "unconnected-(J1-Pad12)") (class "Default")
      (node (ref "J1") (pin "12") (pinfunction "12_12") (pintype "passive+no_connect"))
    )
    (net (code "140") (name "unconnected-(J1-Pad13)") (class "Default")
      (node (ref "J1") (pin "13") (pinfunction "13_13") (pintype "passive+no_connect"))
    )
    (net (code "141") (name "unconnected-(J1-Pad14)") (class "Default")
      (node (ref "J1") (pin "14") (pinfunction "14_14") (pintype "passive+no_connect"))
    )
    (net (code "142") (name "unconnected-(J1-Pad15)") (class "Default")
      (node (ref "J1") (pin "15") (pinfunction "15_15") (pintype "passive+no_connect"))
    )
    (net (code "143") (name "unconnected-(J1-Pad16)") (class "Default")
      (node (ref "J1") (pin "16") (pinfunction "16_16") (pintype "passive+no_connect"))
    )
    (net (code "144") (name "unconnected-(J1-Pad20)") (class "Default")
      (node (ref "J1") (pin "20") (pinfunction "20_20") (pintype "passive+no_connect"))
    )
    (net (code "145") (name "unconnected-(J1-Pad21)") (class "Default")
      (node (ref "J1") (pin "21") (pinfunction "21_21") (pintype "passive+no_connect"))
    )
    (net (code "146") (name "unconnected-(J1-Pad22)") (class "Default")
      (node (ref "J1") (pin "22") (pinfunction "22_22") (pintype "passive+no_connect"))
    )
    (net (code "147") (name "unconnected-(J1-Pad23)") (class "Default")
      (node (ref "J1") (pin "23") (pinfunction "23_23") (pintype "passive+no_connect"))
    )
    (net (code "148") (name "unconnected-(J1-Pad29)") (class "Default")
      (node (ref "J1") (pin "29") (pinfunction "29_29") (pintype "passive+no_connect"))
    )
    (net (code "149") (name "unconnected-(J1-Pad30)") (class "Default")
      (node (ref "J1") (pin "30") (pinfunction "30_30") (pintype "passive+no_connect"))
    )
    (net (code "150") (name "unconnected-(J1-Pad59)") (class "Default")
      (node (ref "J1") (pin "59") (pinfunction "59_59") (pintype "passive+no_connect"))
    )
    (net (code "151") (name "unconnected-(J1-Pad60)") (class "Default")
      (node (ref "J1") (pin "60") (pinfunction "60_60") (pintype "passive+no_connect"))
    )
    (net (code "152") (name "unconnected-(JP4-Pad7)") (class "Default")
      (node (ref "JP4") (pin "7") (pinfunction "7_7") (pintype "passive+no_connect"))
    )
    (net (code "153") (name "unconnected-(JP5-Pad4)") (class "Default")
      (node (ref "JP5") (pin "4") (pinfunction "4_4") (pintype "passive+no_connect"))
    )
    (net (code "154") (name "unconnected-(U9A-LPF-Pad64)") (class "Default")
      (node (ref "U9") (pin "64") (pinfunction "LPF_64") (pintype "passive+no_connect"))
    )
    (net (code "155") (name "unconnected-(X1-EN{slash}NC-Pad1)") (class "Default")
      (node (ref "X1") (pin "1") (pinfunction "EN/NC_1") (pintype "passive+no_connect"))
    )
  )
)
